# Breeze2_ESC_V1.net
KiCad netlist of a schematic drawn in Altium Designer
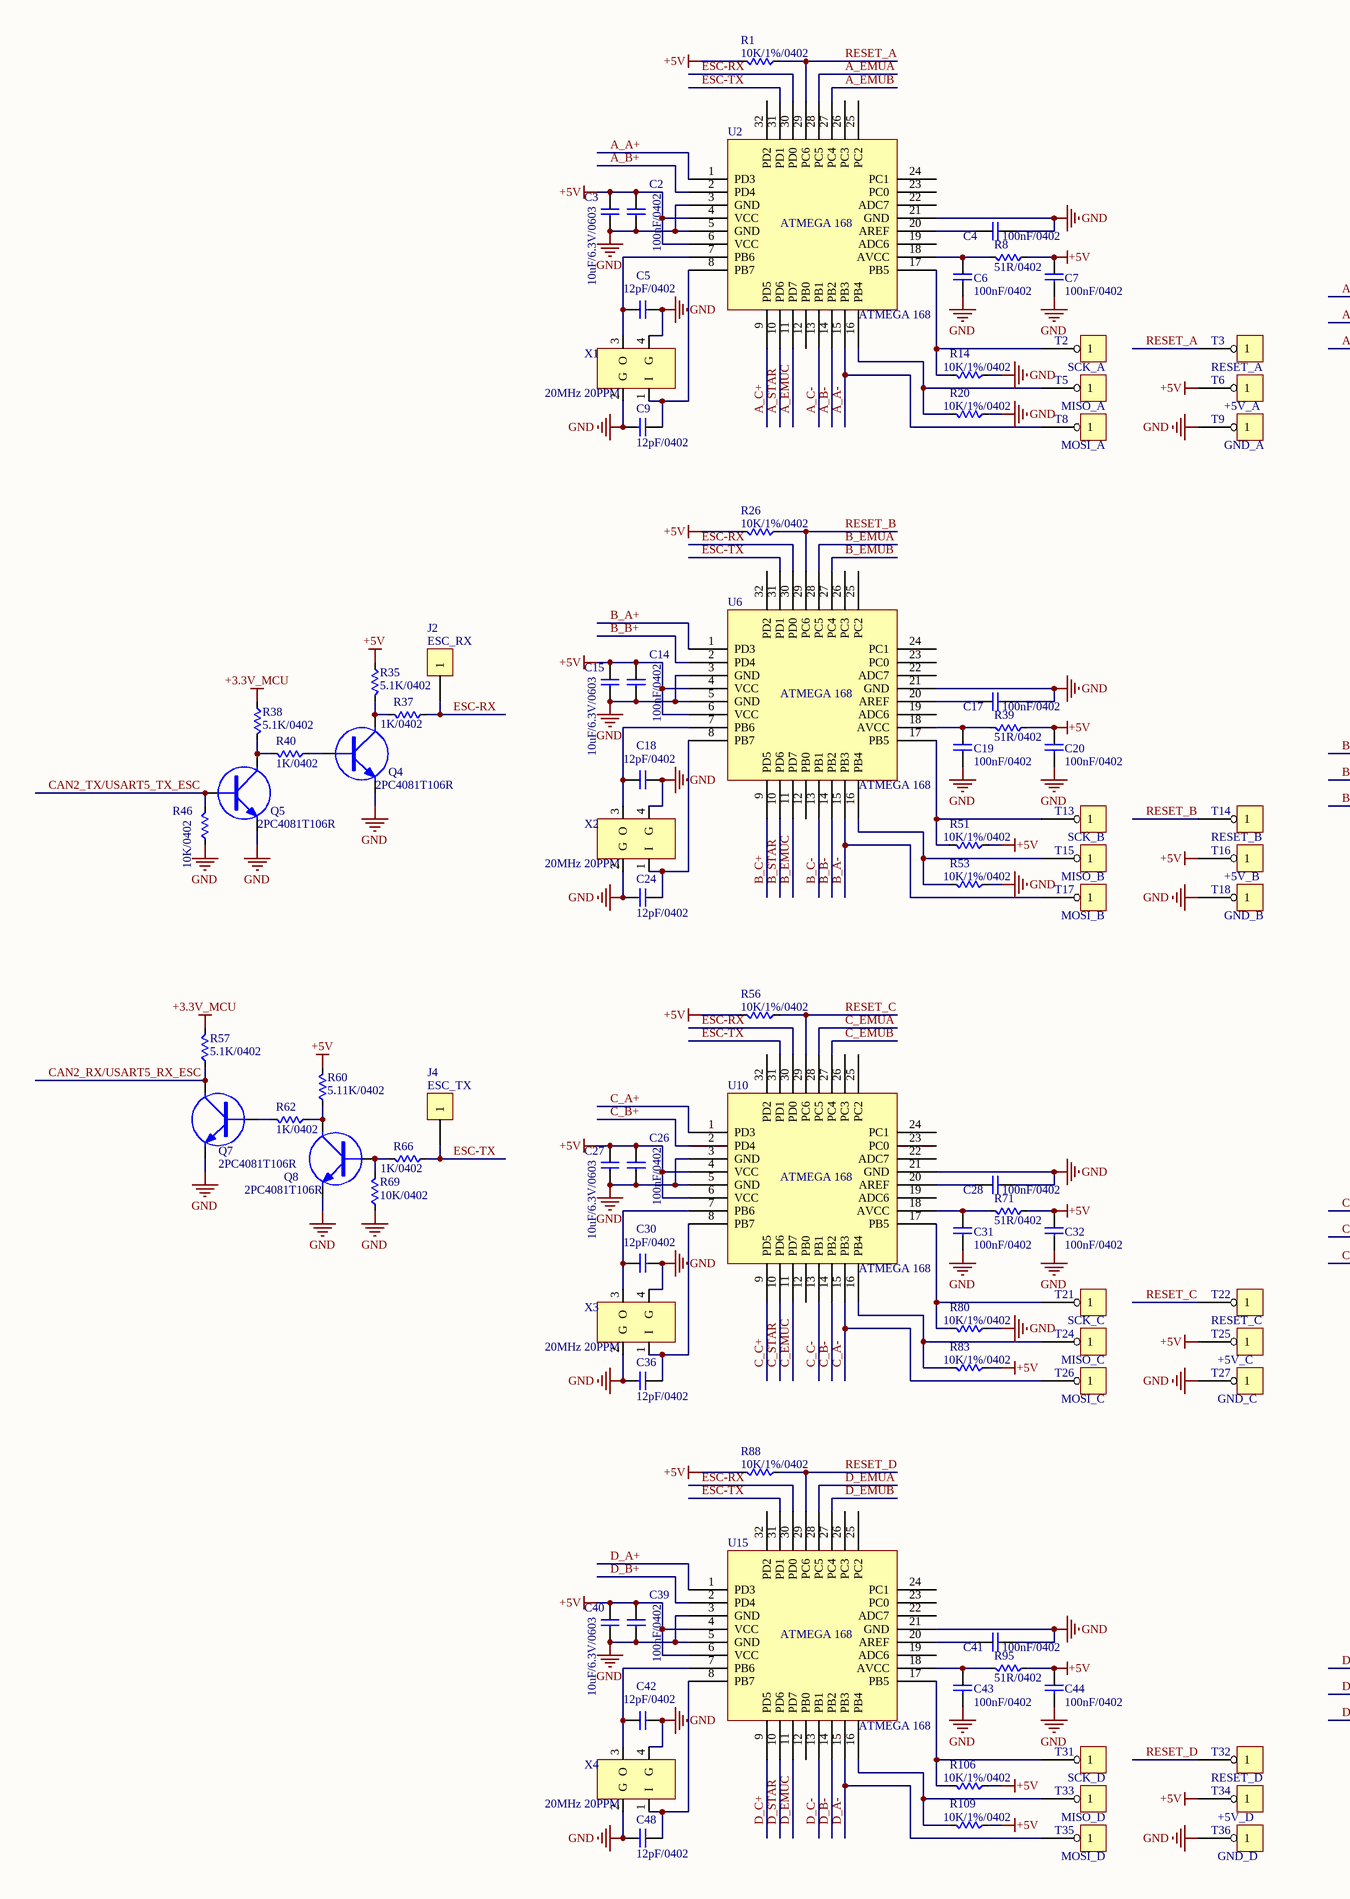
[diagram p0: Breeze2 ESC V1.SchDoc, left]
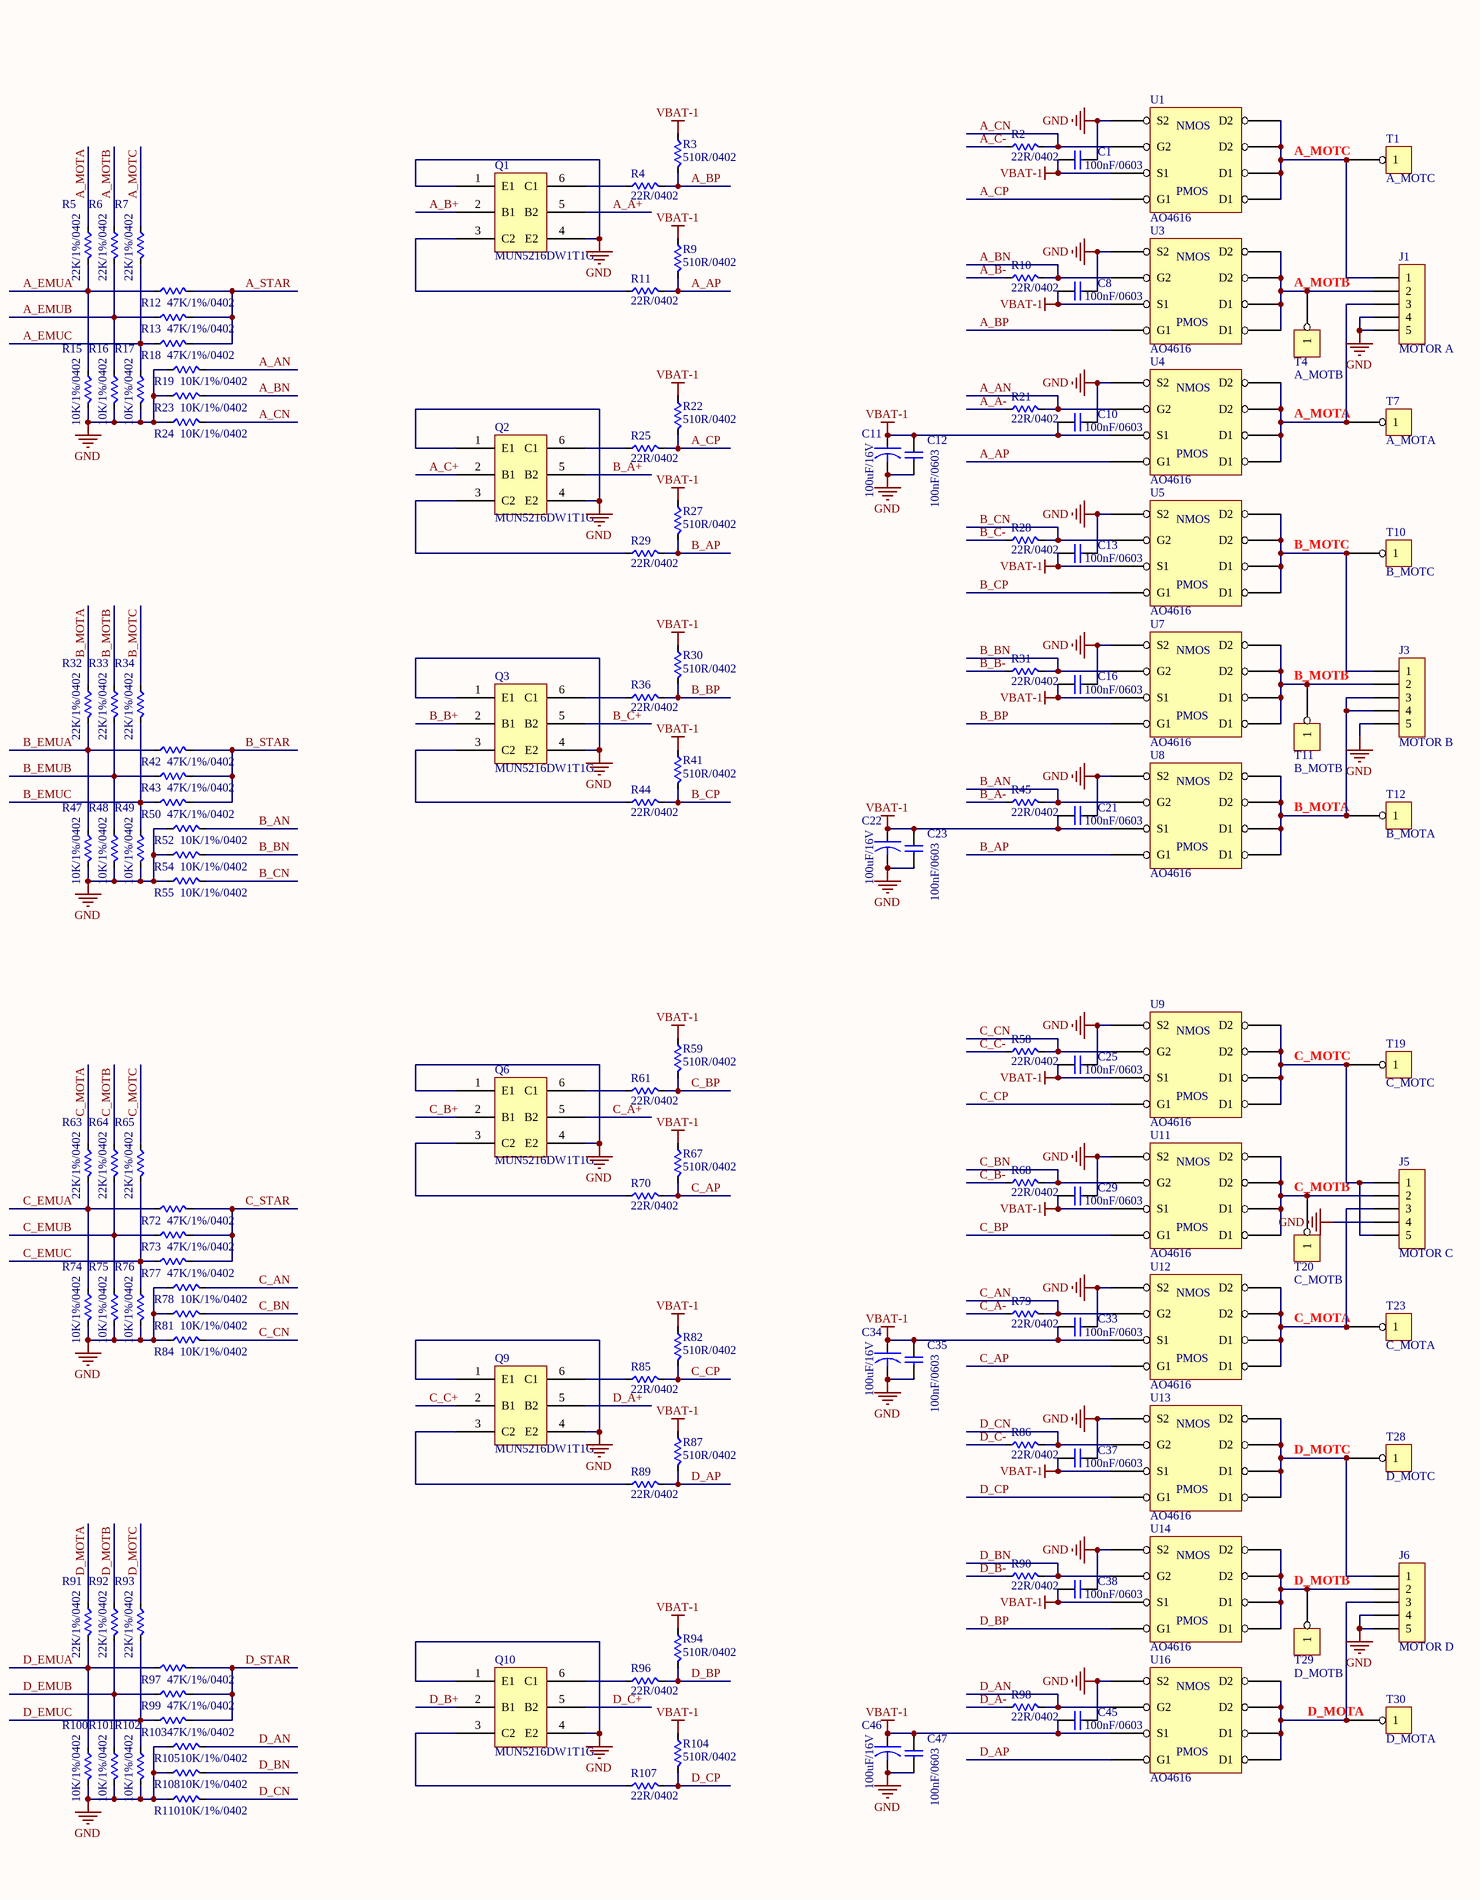
[diagram p1: Breeze2 ESC V1.SchDoc, right]

(export (version "E")
  (design (tool "Eeschema 10.0.6"))
  (components
    (comp (ref "C1")
      (value "100nF/0603")
      (footprint "0603C-S")
      (description "CAP")
      (libsource (lib "YUNEEC-SCH") (part "CAP"))
    )
    (comp (ref "C2")
      (value "100nF/0402")
      (footprint "0402C-S")
      (description "CAP")
      (libsource (lib "YUNEEC-SCH") (part "CAP"))
    )
    (comp (ref "C3")
      (value "10uF/6.3V/0603")
      (footprint "0603C-S")
      (description "CAP")
      (libsource (lib "YUNEEC-SCH") (part "CAP"))
    )
    (comp (ref "C4")
      (value "100nF/0402")
      (footprint "0402C-S")
      (description "CAP")
      (libsource (lib "YUNEEC-SCH") (part "CAP"))
    )
    (comp (ref "C5")
      (value "12pF/0402")
      (footprint "0402C-S")
      (description "CAP")
      (libsource (lib "YUNEEC-SCH") (part "CAP"))
    )
    (comp (ref "C6")
      (value "100nF/0402")
      (footprint "0402C-S")
      (description "CAP")
      (libsource (lib "YUNEEC-SCH") (part "CAP"))
    )
    (comp (ref "C7")
      (value "100nF/0402")
      (footprint "0402C-S")
      (description "CAP")
      (libsource (lib "YUNEEC-SCH") (part "CAP"))
    )
    (comp (ref "C8")
      (value "100nF/0603")
      (footprint "0603C-S")
      (description "CAP")
      (libsource (lib "YUNEEC-SCH") (part "CAP"))
    )
    (comp (ref "C9")
      (value "12pF/0402")
      (footprint "0402C-S")
      (description "CAP")
      (libsource (lib "YUNEEC-SCH") (part "CAP"))
    )
    (comp (ref "C10")
      (value "100nF/0603")
      (footprint "0603C-S")
      (description "CAP")
      (libsource (lib "YUNEEC-SCH") (part "CAP"))
    )
    (comp (ref "C11")
      (value "100uF/16V")
      (footprint "1210C-S")
      (description "Capacitor")
      (libsource (lib "*") (part "CAPACITOR"))
    )
    (comp (ref "C12")
      (value "100nF/0603")
      (footprint "0603C-S")
      (description "CAP")
      (libsource (lib "YUNEEC-SCH") (part "CAP"))
    )
    (comp (ref "C13")
      (value "100nF/0603")
      (footprint "0603C-S")
      (description "CAP")
      (libsource (lib "YUNEEC-SCH") (part "CAP"))
    )
    (comp (ref "C14")
      (value "100nF/0402")
      (footprint "0402C-S")
      (description "CAP")
      (libsource (lib "YUNEEC-SCH") (part "CAP"))
    )
    (comp (ref "C15")
      (value "10uF/6.3V/0603")
      (footprint "0603C-S")
      (description "CAP")
      (libsource (lib "YUNEEC-SCH") (part "CAP"))
    )
    (comp (ref "C16")
      (value "100nF/0603")
      (footprint "0603C-S")
      (description "CAP")
      (libsource (lib "YUNEEC-SCH") (part "CAP"))
    )
    (comp (ref "C17")
      (value "100nF/0402")
      (footprint "0402C-S")
      (description "CAP")
      (libsource (lib "YUNEEC-SCH") (part "CAP"))
    )
    (comp (ref "C18")
      (value "12pF/0402")
      (footprint "0402C-S")
      (description "CAP")
      (libsource (lib "YUNEEC-SCH") (part "CAP"))
    )
    (comp (ref "C19")
      (value "100nF/0402")
      (footprint "0402C-S")
      (description "CAP")
      (libsource (lib "YUNEEC-SCH") (part "CAP"))
    )
    (comp (ref "C20")
      (value "100nF/0402")
      (footprint "0402C-S")
      (description "CAP")
      (libsource (lib "YUNEEC-SCH") (part "CAP"))
    )
    (comp (ref "C21")
      (value "100nF/0603")
      (footprint "0603C-S")
      (description "CAP")
      (libsource (lib "YUNEEC-SCH") (part "CAP"))
    )
    (comp (ref "C22")
      (value "100uF/16V")
      (footprint "1210C-S")
      (description "Capacitor")
      (libsource (lib "*") (part "CAPACITOR"))
    )
    (comp (ref "C23")
      (value "100nF/0603")
      (footprint "0603C-S")
      (description "CAP")
      (libsource (lib "YUNEEC-SCH") (part "CAP"))
    )
    (comp (ref "C24")
      (value "12pF/0402")
      (footprint "0402C-S")
      (description "CAP")
      (libsource (lib "YUNEEC-SCH") (part "CAP"))
    )
    (comp (ref "C25")
      (value "100nF/0603")
      (footprint "0603C-S")
      (description "CAP")
      (libsource (lib "YUNEEC-SCH") (part "CAP"))
    )
    (comp (ref "C26")
      (value "100nF/0402")
      (footprint "0402C-S")
      (description "CAP")
      (libsource (lib "YUNEEC-SCH") (part "CAP"))
    )
    (comp (ref "C27")
      (value "10uF/6.3V/0603")
      (footprint "0603C-S")
      (description "CAP")
      (libsource (lib "YUNEEC-SCH") (part "CAP"))
    )
    (comp (ref "C28")
      (value "100nF/0402")
      (footprint "0402C-S")
      (description "CAP")
      (libsource (lib "YUNEEC-SCH") (part "CAP"))
    )
    (comp (ref "C29")
      (value "100nF/0603")
      (footprint "0603C-S")
      (description "CAP")
      (libsource (lib "YUNEEC-SCH") (part "CAP"))
    )
    (comp (ref "C30")
      (value "12pF/0402")
      (footprint "0402C-S")
      (description "CAP")
      (libsource (lib "YUNEEC-SCH") (part "CAP"))
    )
    (comp (ref "C31")
      (value "100nF/0402")
      (footprint "0402C-S")
      (description "CAP")
      (libsource (lib "YUNEEC-SCH") (part "CAP"))
    )
    (comp (ref "C32")
      (value "100nF/0402")
      (footprint "0402C-S")
      (description "CAP")
      (libsource (lib "YUNEEC-SCH") (part "CAP"))
    )
    (comp (ref "C33")
      (value "100nF/0603")
      (footprint "0603C-S")
      (description "CAP")
      (libsource (lib "YUNEEC-SCH") (part "CAP"))
    )
    (comp (ref "C34")
      (value "100uF/16V")
      (footprint "1210C-S")
      (description "Capacitor")
      (libsource (lib "*") (part "CAPACITOR"))
    )
    (comp (ref "C35")
      (value "100nF/0603")
      (footprint "0603C-S")
      (description "CAP")
      (libsource (lib "YUNEEC-SCH") (part "CAP"))
    )
    (comp (ref "C36")
      (value "12pF/0402")
      (footprint "0402C-S")
      (description "CAP")
      (libsource (lib "YUNEEC-SCH") (part "CAP"))
    )
    (comp (ref "C37")
      (value "100nF/0603")
      (footprint "0603C-S")
      (description "CAP")
      (libsource (lib "YUNEEC-SCH") (part "CAP"))
    )
    (comp (ref "C38")
      (value "100nF/0603")
      (footprint "0603C-S")
      (description "CAP")
      (libsource (lib "YUNEEC-SCH") (part "CAP"))
    )
    (comp (ref "C39")
      (value "100nF/0402")
      (footprint "0402C-S")
      (description "CAP")
      (libsource (lib "YUNEEC-SCH") (part "CAP"))
    )
    (comp (ref "C40")
      (value "10uF/6.3V/0603")
      (footprint "0603C-S")
      (description "CAP")
      (libsource (lib "YUNEEC-SCH") (part "CAP"))
    )
    (comp (ref "C41")
      (value "100nF/0402")
      (footprint "0402C-S")
      (description "CAP")
      (libsource (lib "YUNEEC-SCH") (part "CAP"))
    )
    (comp (ref "C42")
      (value "12pF/0402")
      (footprint "0402C-S")
      (description "CAP")
      (libsource (lib "YUNEEC-SCH") (part "CAP"))
    )
    (comp (ref "C43")
      (value "100nF/0402")
      (footprint "0402C-S")
      (description "CAP")
      (libsource (lib "YUNEEC-SCH") (part "CAP"))
    )
    (comp (ref "C44")
      (value "100nF/0402")
      (footprint "0402C-S")
      (description "CAP")
      (libsource (lib "YUNEEC-SCH") (part "CAP"))
    )
    (comp (ref "C45")
      (value "100nF/0603")
      (footprint "0603C-S")
      (description "CAP")
      (libsource (lib "YUNEEC-SCH") (part "CAP"))
    )
    (comp (ref "C46")
      (value "100uF/16V")
      (footprint "1210C-S")
      (description "Capacitor")
      (libsource (lib "*") (part "CAPACITOR"))
    )
    (comp (ref "C47")
      (value "100nF/0603")
      (footprint "0603C-S")
      (description "CAP")
      (libsource (lib "YUNEEC-SCH") (part "CAP"))
    )
    (comp (ref "C48")
      (value "12pF/0402")
      (footprint "0402C-S")
      (description "CAP")
      (libsource (lib "YUNEEC-SCH") (part "CAP"))
    )
    (comp (ref "J1")
      (value "MOTOR A")
      (footprint "1.5*3PIN/SMD-H")
      (description "Connector")
      (libsource (lib "YUNEEC-SCH") (part "CON5"))
    )
    (comp (ref "J2")
      (value "ESC_RX")
      (footprint "TPJ1.2")
      (description "Connector")
      (libsource (lib "*") (part "CON1"))
    )
    (comp (ref "J3")
      (value "MOTOR B")
      (footprint "1.5*3PIN/SMD-H")
      (description "Connector")
      (libsource (lib "YUNEEC-SCH") (part "CON5"))
    )
    (comp (ref "J4")
      (value "ESC_TX")
      (footprint "TPJ1.2")
      (description "Connector")
      (libsource (lib "*") (part "CON1"))
    )
    (comp (ref "J5")
      (value "MOTOR C")
      (footprint "1.5*3PIN/SMD-H")
      (description "Connector")
      (libsource (lib "YUNEEC-SCH") (part "CON5"))
    )
    (comp (ref "J6")
      (value "MOTOR D")
      (footprint "1.5*3PIN/SMD-H")
      (description "Connector")
      (libsource (lib "YUNEEC-SCH") (part "CON5"))
    )
    (comp (ref "Q1") (value "MUN5216DW1T1G") (footprint "SOT-363A") (libsource (lib "*") (part "NPN_6")))
    (comp (ref "Q2") (value "MUN5216DW1T1G") (footprint "SOT-363A") (libsource (lib "*") (part "NPN_6")))
    (comp (ref "Q3") (value "MUN5216DW1T1G") (footprint "SOT-363A") (libsource (lib "*") (part "NPN_6")))
    (comp (ref "Q4")
      (value "2PC4081T106R")
      (footprint "SOT-323A")
      (description "NPN Transistor")
      (libsource (lib "YUNEEC-SCH") (part "NPN"))
    )
    (comp (ref "Q5")
      (value "2PC4081T106R")
      (footprint "SOT-323A")
      (description "NPN Transistor")
      (libsource (lib "YUNEEC-SCH") (part "NPN"))
    )
    (comp (ref "Q6") (value "MUN5216DW1T1G") (footprint "SOT-363A") (libsource (lib "*") (part "NPN_6")))
    (comp (ref "Q7")
      (value "2PC4081T106R")
      (footprint "SOT-323A")
      (description "NPN Transistor")
      (libsource (lib "YUNEEC-SCH") (part "NPN"))
    )
    (comp (ref "Q8")
      (value "2PC4081T106R")
      (footprint "SOT-323A")
      (description "NPN Transistor")
      (libsource (lib "YUNEEC-SCH") (part "NPN"))
    )
    (comp (ref "Q9") (value "MUN5216DW1T1G") (footprint "SOT-363A") (libsource (lib "*") (part "NPN_6")))
    (comp (ref "Q10") (value "MUN5216DW1T1G") (footprint "SOT-363A") (libsource (lib "*") (part "NPN_6")))
    (comp (ref "R1") (value "10K/1%/0402") (footprint "0402R-S") (libsource (lib "YUNEEC-SCH") (part "RES")))
    (comp (ref "R2") (value "22R/0402") (footprint "0402R-S") (libsource (lib "YUNEEC-SCH") (part "RES")))
    (comp (ref "R3") (value "510R/0402") (footprint "0402R-S") (libsource (lib "YUNEEC-SCH") (part "RES")))
    (comp (ref "R4") (value "22R/0402") (footprint "0402R-S") (libsource (lib "YUNEEC-SCH") (part "RES")))
    (comp (ref "R5") (value "22K/1%/0402") (footprint "0402R-S") (libsource (lib "YUNEEC-SCH") (part "RES")))
    (comp (ref "R6") (value "22K/1%/0402") (footprint "0402R-S") (libsource (lib "YUNEEC-SCH") (part "RES")))
    (comp (ref "R7") (value "22K/1%/0402") (footprint "0402R-S") (libsource (lib "YUNEEC-SCH") (part "RES")))
    (comp (ref "R8") (value "51R/0402") (footprint "0402R-S") (libsource (lib "YUNEEC-SCH") (part "RES")))
    (comp (ref "R9") (value "510R/0402") (footprint "0402R-S") (libsource (lib "YUNEEC-SCH") (part "RES")))
    (comp (ref "R10") (value "22R/0402") (footprint "0402R-S") (libsource (lib "YUNEEC-SCH") (part "RES")))
    (comp (ref "R11") (value "22R/0402") (footprint "0402R-S") (libsource (lib "YUNEEC-SCH") (part "RES")))
    (comp (ref "R12") (value "47K/1%/0402") (footprint "0402R-S") (libsource (lib "YUNEEC-SCH") (part "RES")))
    (comp (ref "R13") (value "47K/1%/0402") (footprint "0402R-S") (libsource (lib "YUNEEC-SCH") (part "RES")))
    (comp (ref "R14") (value "10K/1%/0402") (footprint "0402R-S") (libsource (lib "YUNEEC-SCH") (part "RES")))
    (comp (ref "R15") (value "10K/1%/0402") (footprint "0402R-S") (libsource (lib "YUNEEC-SCH") (part "RES")))
    (comp (ref "R16") (value "10K/1%/0402") (footprint "0402R-S") (libsource (lib "YUNEEC-SCH") (part "RES")))
    (comp (ref "R17") (value "10K/1%/0402") (footprint "0402R-S") (libsource (lib "YUNEEC-SCH") (part "RES")))
    (comp (ref "R18") (value "47K/1%/0402") (footprint "0402R-S") (libsource (lib "YUNEEC-SCH") (part "RES")))
    (comp (ref "R19") (value "10K/1%/0402") (footprint "0402R-S") (libsource (lib "YUNEEC-SCH") (part "RES")))
    (comp (ref "R20") (value "10K/1%/0402") (footprint "0402R-S") (libsource (lib "YUNEEC-SCH") (part "RES")))
    (comp (ref "R21") (value "22R/0402") (footprint "0402R-S") (libsource (lib "YUNEEC-SCH") (part "RES")))
    (comp (ref "R22") (value "510R/0402") (footprint "0402R-S") (libsource (lib "YUNEEC-SCH") (part "RES")))
    (comp (ref "R23") (value "10K/1%/0402") (footprint "0402R-S") (libsource (lib "YUNEEC-SCH") (part "RES")))
    (comp (ref "R24") (value "10K/1%/0402") (footprint "0402R-S") (libsource (lib "YUNEEC-SCH") (part "RES")))
    (comp (ref "R25") (value "22R/0402") (footprint "0402R-S") (libsource (lib "YUNEEC-SCH") (part "RES")))
    (comp (ref "R26") (value "10K/1%/0402") (footprint "0402R-S") (libsource (lib "YUNEEC-SCH") (part "RES")))
    (comp (ref "R27") (value "510R/0402") (footprint "0402R-S") (libsource (lib "YUNEEC-SCH") (part "RES")))
    (comp (ref "R28") (value "22R/0402") (footprint "0402R-S") (libsource (lib "YUNEEC-SCH") (part "RES")))
    (comp (ref "R29") (value "22R/0402") (footprint "0402R-S") (libsource (lib "YUNEEC-SCH") (part "RES")))
    (comp (ref "R30") (value "510R/0402") (footprint "0402R-S") (libsource (lib "YUNEEC-SCH") (part "RES")))
    (comp (ref "R31") (value "22R/0402") (footprint "0402R-S") (libsource (lib "YUNEEC-SCH") (part "RES")))
    (comp (ref "R32") (value "22K/1%/0402") (footprint "0402R-S") (libsource (lib "YUNEEC-SCH") (part "RES")))
    (comp (ref "R33") (value "22K/1%/0402") (footprint "0402R-S") (libsource (lib "YUNEEC-SCH") (part "RES")))
    (comp (ref "R34") (value "22K/1%/0402") (footprint "0402R-S") (libsource (lib "YUNEEC-SCH") (part "RES")))
    (comp (ref "R35") (value "5.1K/0402") (footprint "0402R-S") (libsource (lib "YUNEEC-SCH") (part "RES")))
    (comp (ref "R36") (value "22R/0402") (footprint "0402R-S") (libsource (lib "YUNEEC-SCH") (part "RES")))
    (comp (ref "R37") (value "1K/0402") (footprint "0402R-S") (libsource (lib "YUNEEC-SCH") (part "RES")))
    (comp (ref "R38") (value "5.1K/0402") (footprint "0402R-S") (libsource (lib "YUNEEC-SCH") (part "RES")))
    (comp (ref "R39") (value "51R/0402") (footprint "0402R-S") (libsource (lib "YUNEEC-SCH") (part "RES")))
    (comp (ref "R40") (value "1K/0402") (footprint "0402R-S") (libsource (lib "YUNEEC-SCH") (part "RES")))
    (comp (ref "R41") (value "510R/0402") (footprint "0402R-S") (libsource (lib "YUNEEC-SCH") (part "RES")))
    (comp (ref "R42") (value "47K/1%/0402") (footprint "0402R-S") (libsource (lib "YUNEEC-SCH") (part "RES")))
    (comp (ref "R43") (value "47K/1%/0402") (footprint "0402R-S") (libsource (lib "YUNEEC-SCH") (part "RES")))
    (comp (ref "R44") (value "22R/0402") (footprint "0402R-S") (libsource (lib "YUNEEC-SCH") (part "RES")))
    (comp (ref "R45") (value "22R/0402") (footprint "0402R-S") (libsource (lib "YUNEEC-SCH") (part "RES")))
    (comp (ref "R46") (value "10K/0402") (footprint "0402R-S") (libsource (lib "YUNEEC-SCH") (part "RES")))
    (comp (ref "R47") (value "10K/1%/0402") (footprint "0402R-S") (libsource (lib "YUNEEC-SCH") (part "RES")))
    (comp (ref "R48") (value "10K/1%/0402") (footprint "0402R-S") (libsource (lib "YUNEEC-SCH") (part "RES")))
    (comp (ref "R49") (value "10K/1%/0402") (footprint "0402R-S") (libsource (lib "YUNEEC-SCH") (part "RES")))
    (comp (ref "R50") (value "47K/1%/0402") (footprint "0402R-S") (libsource (lib "YUNEEC-SCH") (part "RES")))
    (comp (ref "R51") (value "10K/1%/0402") (footprint "0402R-S") (libsource (lib "YUNEEC-SCH") (part "RES")))
    (comp (ref "R52") (value "10K/1%/0402") (footprint "0402R-S") (libsource (lib "YUNEEC-SCH") (part "RES")))
    (comp (ref "R53") (value "10K/1%/0402") (footprint "0402R-S") (libsource (lib "YUNEEC-SCH") (part "RES")))
    (comp (ref "R54") (value "10K/1%/0402") (footprint "0402R-S") (libsource (lib "YUNEEC-SCH") (part "RES")))
    (comp (ref "R55") (value "10K/1%/0402") (footprint "0402R-S") (libsource (lib "YUNEEC-SCH") (part "RES")))
    (comp (ref "R56") (value "10K/1%/0402") (footprint "0402R-S") (libsource (lib "YUNEEC-SCH") (part "RES")))
    (comp (ref "R57") (value "5.1K/0402") (footprint "0402R-S") (libsource (lib "YUNEEC-SCH") (part "RES")))
    (comp (ref "R58") (value "22R/0402") (footprint "0402R-S") (libsource (lib "YUNEEC-SCH") (part "RES")))
    (comp (ref "R59") (value "510R/0402") (footprint "0402R-S") (libsource (lib "YUNEEC-SCH") (part "RES")))
    (comp (ref "R60") (value "5.11K/0402") (footprint "0402R-S") (libsource (lib "YUNEEC-SCH") (part "RES")))
    (comp (ref "R61") (value "22R/0402") (footprint "0402R-S") (libsource (lib "YUNEEC-SCH") (part "RES")))
    (comp (ref "R62") (value "1K/0402") (footprint "0402R-S") (libsource (lib "YUNEEC-SCH") (part "RES")))
    (comp (ref "R63") (value "22K/1%/0402") (footprint "0402R-S") (libsource (lib "YUNEEC-SCH") (part "RES")))
    (comp (ref "R64") (value "22K/1%/0402") (footprint "0402R-S") (libsource (lib "YUNEEC-SCH") (part "RES")))
    (comp (ref "R65") (value "22K/1%/0402") (footprint "0402R-S") (libsource (lib "YUNEEC-SCH") (part "RES")))
    (comp (ref "R66") (value "1K/0402") (footprint "0402R-S") (libsource (lib "YUNEEC-SCH") (part "RES")))
    (comp (ref "R67") (value "510R/0402") (footprint "0402R-S") (libsource (lib "YUNEEC-SCH") (part "RES")))
    (comp (ref "R68") (value "22R/0402") (footprint "0402R-S") (libsource (lib "YUNEEC-SCH") (part "RES")))
    (comp (ref "R69") (value "10K/0402") (footprint "0402R-S") (libsource (lib "YUNEEC-SCH") (part "RES")))
    (comp (ref "R70") (value "22R/0402") (footprint "0402R-S") (libsource (lib "YUNEEC-SCH") (part "RES")))
    (comp (ref "R71") (value "51R/0402") (footprint "0402R-S") (libsource (lib "YUNEEC-SCH") (part "RES")))
    (comp (ref "R72") (value "47K/1%/0402") (footprint "0402R-S") (libsource (lib "YUNEEC-SCH") (part "RES")))
    (comp (ref "R73") (value "47K/1%/0402") (footprint "0402R-S") (libsource (lib "YUNEEC-SCH") (part "RES")))
    (comp (ref "R74") (value "10K/1%/0402") (footprint "0402R-S") (libsource (lib "YUNEEC-SCH") (part "RES")))
    (comp (ref "R75") (value "10K/1%/0402") (footprint "0402R-S") (libsource (lib "YUNEEC-SCH") (part "RES")))
    (comp (ref "R76") (value "10K/1%/0402") (footprint "0402R-S") (libsource (lib "YUNEEC-SCH") (part "RES")))
    (comp (ref "R77") (value "47K/1%/0402") (footprint "0402R-S") (libsource (lib "YUNEEC-SCH") (part "RES")))
    (comp (ref "R78") (value "10K/1%/0402") (footprint "0402R-S") (libsource (lib "YUNEEC-SCH") (part "RES")))
    (comp (ref "R79") (value "22R/0402") (footprint "0402R-S") (libsource (lib "YUNEEC-SCH") (part "RES")))
    (comp (ref "R80") (value "10K/1%/0402") (footprint "0402R-S") (libsource (lib "YUNEEC-SCH") (part "RES")))
    (comp (ref "R81") (value "10K/1%/0402") (footprint "0402R-S") (libsource (lib "YUNEEC-SCH") (part "RES")))
    (comp (ref "R82") (value "510R/0402") (footprint "0402R-S") (libsource (lib "YUNEEC-SCH") (part "RES")))
    (comp (ref "R83") (value "10K/1%/0402") (footprint "0402R-S") (libsource (lib "YUNEEC-SCH") (part "RES")))
    (comp (ref "R84") (value "10K/1%/0402") (footprint "0402R-S") (libsource (lib "YUNEEC-SCH") (part "RES")))
    (comp (ref "R85") (value "22R/0402") (footprint "0402R-S") (libsource (lib "YUNEEC-SCH") (part "RES")))
    (comp (ref "R86") (value "22R/0402") (footprint "0402R-S") (libsource (lib "YUNEEC-SCH") (part "RES")))
    (comp (ref "R87") (value "510R/0402") (footprint "0402R-S") (libsource (lib "YUNEEC-SCH") (part "RES")))
    (comp (ref "R88") (value "10K/1%/0402") (footprint "0402R-S") (libsource (lib "YUNEEC-SCH") (part "RES")))
    (comp (ref "R89") (value "22R/0402") (footprint "0402R-S") (libsource (lib "YUNEEC-SCH") (part "RES")))
    (comp (ref "R90") (value "22R/0402") (footprint "0402R-S") (libsource (lib "YUNEEC-SCH") (part "RES")))
    (comp (ref "R91") (value "22K/1%/0402") (footprint "0402R-S") (libsource (lib "YUNEEC-SCH") (part "RES")))
    (comp (ref "R92") (value "22K/1%/0402") (footprint "0402R-S") (libsource (lib "YUNEEC-SCH") (part "RES")))
    (comp (ref "R93") (value "22K/1%/0402") (footprint "0402R-S") (libsource (lib "YUNEEC-SCH") (part "RES")))
    (comp (ref "R94") (value "510R/0402") (footprint "0402R-S") (libsource (lib "YUNEEC-SCH") (part "RES")))
    (comp (ref "R95") (value "51R/0402") (footprint "0402R-S") (libsource (lib "YUNEEC-SCH") (part "RES")))
    (comp (ref "R96") (value "22R/0402") (footprint "0402R-S") (libsource (lib "YUNEEC-SCH") (part "RES")))
    (comp (ref "R97") (value "47K/1%/0402") (footprint "0402R-S") (libsource (lib "YUNEEC-SCH") (part "RES")))
    (comp (ref "R98") (value "22R/0402") (footprint "0402R-S") (libsource (lib "YUNEEC-SCH") (part "RES")))
    (comp (ref "R99") (value "47K/1%/0402") (footprint "0402R-S") (libsource (lib "YUNEEC-SCH") (part "RES")))
    (comp (ref "R100")
      (value "10K/1%/0402")
      (footprint "0402R-S")
      (libsource (lib "YUNEEC-SCH") (part "RES"))
    )
    (comp (ref "R101")
      (value "10K/1%/0402")
      (footprint "0402R-S")
      (libsource (lib "YUNEEC-SCH") (part "RES"))
    )
    (comp (ref "R102")
      (value "10K/1%/0402")
      (footprint "0402R-S")
      (libsource (lib "YUNEEC-SCH") (part "RES"))
    )
    (comp (ref "R103")
      (value "47K/1%/0402")
      (footprint "0402R-S")
      (libsource (lib "YUNEEC-SCH") (part "RES"))
    )
    (comp (ref "R104") (value "510R/0402") (footprint "0402R-S") (libsource (lib "YUNEEC-SCH") (part "RES")))
    (comp (ref "R105")
      (value "10K/1%/0402")
      (footprint "0402R-S")
      (libsource (lib "YUNEEC-SCH") (part "RES"))
    )
    (comp (ref "R106")
      (value "10K/1%/0402")
      (footprint "0402R-S")
      (libsource (lib "YUNEEC-SCH") (part "RES"))
    )
    (comp (ref "R107") (value "22R/0402") (footprint "0402R-S") (libsource (lib "YUNEEC-SCH") (part "RES")))
    (comp (ref "R108")
      (value "10K/1%/0402")
      (footprint "0402R-S")
      (libsource (lib "YUNEEC-SCH") (part "RES"))
    )
    (comp (ref "R109")
      (value "10K/1%/0402")
      (footprint "0402R-S")
      (libsource (lib "YUNEEC-SCH") (part "RES"))
    )
    (comp (ref "R110")
      (value "10K/1%/0402")
      (footprint "0402R-S")
      (libsource (lib "YUNEEC-SCH") (part "RES"))
    )
    (comp (ref "T1") (value "A_MOTC") (footprint "TPJ1.5") (libsource (lib "*") (part "HEADER1")))
    (comp (ref "T2") (value "SCK_A") (footprint "TPJ1.2") (libsource (lib "*") (part "HEADER1")))
    (comp (ref "T3") (value "RESET_A") (footprint "TPJ1.2") (libsource (lib "*") (part "HEADER1")))
    (comp (ref "T4") (value "A_MOTB") (footprint "TPJ1.5") (libsource (lib "") (part "HEADER1_1")))
    (comp (ref "T5") (value "MISO_A") (footprint "TPJ1.2") (libsource (lib "*") (part "HEADER1")))
    (comp (ref "T6") (value "+5V_A") (footprint "TPJ1.2") (libsource (lib "*") (part "HEADER1")))
    (comp (ref "T7") (value "A_MOTA") (footprint "TPJ1.5") (libsource (lib "*") (part "HEADER1")))
    (comp (ref "T8") (value "MOSI_A") (footprint "TPJ1.2") (libsource (lib "*") (part "HEADER1")))
    (comp (ref "T9") (value "GND_A") (footprint "TPJ1.2") (libsource (lib "*") (part "HEADER1")))
    (comp (ref "T10") (value "B_MOTC") (footprint "TPJ1.5") (libsource (lib "*") (part "HEADER1")))
    (comp (ref "T11") (value "B_MOTB") (footprint "TPJ1.5") (libsource (lib "") (part "HEADER1_1")))
    (comp (ref "T12") (value "B_MOTA") (footprint "TPJ1.5") (libsource (lib "*") (part "HEADER1")))
    (comp (ref "T13") (value "SCK_B") (footprint "TPJ1.2") (libsource (lib "*") (part "HEADER1")))
    (comp (ref "T14") (value "RESET_B") (footprint "TPJ1.2") (libsource (lib "*") (part "HEADER1")))
    (comp (ref "T15") (value "MISO_B") (footprint "TPJ1.2") (libsource (lib "*") (part "HEADER1")))
    (comp (ref "T16") (value "+5V_B") (footprint "TPJ1.2") (libsource (lib "*") (part "HEADER1")))
    (comp (ref "T17") (value "MOSI_B") (footprint "TPJ1.2") (libsource (lib "*") (part "HEADER1")))
    (comp (ref "T18") (value "GND_B") (footprint "TPJ1.2") (libsource (lib "*") (part "HEADER1")))
    (comp (ref "T19") (value "C_MOTC") (footprint "TPJ1.5") (libsource (lib "*") (part "HEADER1")))
    (comp (ref "T20") (value "C_MOTB") (footprint "TPJ1.5") (libsource (lib "") (part "HEADER1_1")))
    (comp (ref "T21") (value "SCK_C") (footprint "TPJ1.2") (libsource (lib "*") (part "HEADER1")))
    (comp (ref "T22") (value "RESET_C") (footprint "TPJ1.2") (libsource (lib "*") (part "HEADER1")))
    (comp (ref "T23") (value "C_MOTA") (footprint "TPJ1.5") (libsource (lib "*") (part "HEADER1")))
    (comp (ref "T24") (value "MISO_C") (footprint "TPJ1.2") (libsource (lib "*") (part "HEADER1")))
    (comp (ref "T25") (value "+5V_C") (footprint "TPJ1.2") (libsource (lib "*") (part "HEADER1")))
    (comp (ref "T26") (value "MOSI_C") (footprint "TPJ1.2") (libsource (lib "*") (part "HEADER1")))
    (comp (ref "T27") (value "GND_C") (footprint "TPJ1.2") (libsource (lib "*") (part "HEADER1")))
    (comp (ref "T28") (value "D_MOTC") (footprint "TPJ1.5") (libsource (lib "*") (part "HEADER1")))
    (comp (ref "T29") (value "D_MOTB") (footprint "TPJ1.5") (libsource (lib "") (part "HEADER1_1")))
    (comp (ref "T30") (value "D_MOTA") (footprint "TPJ1.5") (libsource (lib "*") (part "HEADER1")))
    (comp (ref "T31") (value "SCK_D") (footprint "TPJ1.2") (libsource (lib "*") (part "HEADER1")))
    (comp (ref "T32") (value "RESET_D") (footprint "TPJ1.2") (libsource (lib "*") (part "HEADER1")))
    (comp (ref "T33") (value "MISO_D") (footprint "TPJ1.2") (libsource (lib "*") (part "HEADER1")))
    (comp (ref "T34") (value "+5V_D") (footprint "TPJ1.2") (libsource (lib "*") (part "HEADER1")))
    (comp (ref "T35") (value "MOSI_D") (footprint "TPJ1.2") (libsource (lib "*") (part "HEADER1")))
    (comp (ref "T36") (value "GND_D") (footprint "TPJ1.2") (libsource (lib "*") (part "HEADER1")))
    (comp (ref "U1") (value "AO4616") (footprint "SO-8A") (libsource (lib "*") (part "AO4616")))
    (comp (ref "U2") (value "ATMEGA 168") (footprint "QFN32/5*5") (libsource (lib "*") (part "ATMEGA 168")))
    (comp (ref "U3") (value "AO4616") (footprint "SO-8A") (libsource (lib "*") (part "AO4616")))
    (comp (ref "U4") (value "AO4616") (footprint "SO-8A") (libsource (lib "*") (part "AO4616")))
    (comp (ref "U5") (value "AO4616") (footprint "SO-8A") (libsource (lib "*") (part "AO4616")))
    (comp (ref "U6") (value "ATMEGA 168") (footprint "QFN32/5*5") (libsource (lib "*") (part "ATMEGA 168")))
    (comp (ref "U7") (value "AO4616") (footprint "SO-8A") (libsource (lib "*") (part "AO4616")))
    (comp (ref "U8") (value "AO4616") (footprint "SO-8A") (libsource (lib "*") (part "AO4616")))
    (comp (ref "U9") (value "AO4616") (footprint "SO-8A") (libsource (lib "*") (part "AO4616")))
    (comp (ref "U10") (value "ATMEGA 168") (footprint "QFN32/5*5") (libsource (lib "*") (part "ATMEGA 168")))
    (comp (ref "U11") (value "AO4616") (footprint "SO-8A") (libsource (lib "*") (part "AO4616")))
    (comp (ref "U12") (value "AO4616") (footprint "SO-8A") (libsource (lib "*") (part "AO4616")))
    (comp (ref "U13") (value "AO4616") (footprint "SO-8A") (libsource (lib "*") (part "AO4616")))
    (comp (ref "U14") (value "AO4616") (footprint "SO-8A") (libsource (lib "*") (part "AO4616")))
    (comp (ref "U15") (value "ATMEGA 168") (footprint "QFN32/5*5") (libsource (lib "*") (part "ATMEGA 168")))
    (comp (ref "U16") (value "AO4616") (footprint "SO-8A") (libsource (lib "*") (part "AO4616")))
    (comp (ref "X1") (value "20MHz 20PPM") (footprint "Y3225") (libsource (lib "*") (part "CON4A_1")))
    (comp (ref "X2") (value "20MHz 20PPM") (footprint "Y3225") (libsource (lib "*") (part "CON4A_1")))
    (comp (ref "X3") (value "20MHz 20PPM") (footprint "Y3225") (libsource (lib "*") (part "CON4A_1")))
    (comp (ref "X4") (value "20MHz 20PPM") (footprint "Y3225") (libsource (lib "*") (part "CON4A_1")))
  )
  (nets
    (net (code "1") (name "+3.3V_MCU") (class "Default")
      (node (ref "R38") (pin "2") (pinfunction "2_2") (pintype "passive"))
      (node (ref "R57") (pin "2") (pinfunction "2_2") (pintype "passive"))
    )
    (net (code "2") (name "+5V") (class "Default")
      (node (ref "C14") (pin "1") (pinfunction "1_1") (pintype "passive"))
      (node (ref "C15") (pin "1") (pinfunction "1_1") (pintype "passive"))
      (node (ref "C2") (pin "1") (pinfunction "1_1") (pintype "passive"))
      (node (ref "C20") (pin "1") (pinfunction "1_1") (pintype "passive"))
      (node (ref "C26") (pin "1") (pinfunction "1_1") (pintype "passive"))
      (node (ref "C27") (pin "1") (pinfunction "1_1") (pintype "passive"))
      (node (ref "C3") (pin "1") (pinfunction "1_1") (pintype "passive"))
      (node (ref "C32") (pin "1") (pinfunction "1_1") (pintype "passive"))
      (node (ref "C39") (pin "1") (pinfunction "1_1") (pintype "passive"))
      (node (ref "C40") (pin "1") (pinfunction "1_1") (pintype "passive"))
      (node (ref "C44") (pin "1") (pinfunction "1_1") (pintype "passive"))
      (node (ref "C7") (pin "1") (pinfunction "1_1") (pintype "passive"))
      (node (ref "R1") (pin "2") (pinfunction "2_2") (pintype "passive"))
      (node (ref "R106") (pin "1") (pinfunction "1_1") (pintype "passive"))
      (node (ref "R109") (pin "1") (pinfunction "1_1") (pintype "passive"))
      (node (ref "R26") (pin "2") (pinfunction "2_2") (pintype "passive"))
      (node (ref "R35") (pin "2") (pinfunction "2_2") (pintype "passive"))
      (node (ref "R39") (pin "1") (pinfunction "1_1") (pintype "passive"))
      (node (ref "R51") (pin "1") (pinfunction "1_1") (pintype "passive"))
      (node (ref "R56") (pin "2") (pinfunction "2_2") (pintype "passive"))
      (node (ref "R60") (pin "2") (pinfunction "2_2") (pintype "passive"))
      (node (ref "R71") (pin "1") (pinfunction "1_1") (pintype "passive"))
      (node (ref "R8") (pin "1") (pinfunction "1_1") (pintype "passive"))
      (node (ref "R83") (pin "1") (pinfunction "1_1") (pintype "passive"))
      (node (ref "R88") (pin "2") (pinfunction "2_2") (pintype "passive"))
      (node (ref "R95") (pin "1") (pinfunction "1_1") (pintype "passive"))
      (node (ref "T16") (pin "1") (pinfunction "1_1") (pintype "passive"))
      (node (ref "T25") (pin "1") (pinfunction "1_1") (pintype "passive"))
      (node (ref "T34") (pin "1") (pinfunction "1_1") (pintype "passive"))
      (node (ref "T6") (pin "1") (pinfunction "1_1") (pintype "passive"))
      (node (ref "U10") (pin "4") (pinfunction "VCC_4") (pintype "passive"))
      (node (ref "U10") (pin "6") (pinfunction "VCC_6") (pintype "passive"))
      (node (ref "U15") (pin "4") (pinfunction "VCC_4") (pintype "passive"))
      (node (ref "U15") (pin "6") (pinfunction "VCC_6") (pintype "passive"))
      (node (ref "U2") (pin "4") (pinfunction "VCC_4") (pintype "passive"))
      (node (ref "U2") (pin "6") (pinfunction "VCC_6") (pintype "passive"))
      (node (ref "U6") (pin "4") (pinfunction "VCC_4") (pintype "passive"))
      (node (ref "U6") (pin "6") (pinfunction "VCC_6") (pintype "passive"))
    )
    (net (code "3") (name "/A_A+") (class "Default")
      (node (ref "Q1") (pin "5") (pinfunction "B2_5") (pintype "passive"))
      (node (ref "U2") (pin "1") (pinfunction "PD3_1") (pintype "passive"))
    )
    (net (code "4") (name "/A_A-") (class "Default")
      (node (ref "R21") (pin "1") (pinfunction "1_1") (pintype "passive"))
      (node (ref "T8") (pin "1") (pinfunction "1_1") (pintype "passive"))
      (node (ref "U2") (pin "15") (pinfunction "PB3_15") (pintype "passive"))
    )
    (net (code "5") (name "/A_AN") (class "Default")
      (node (ref "R19") (pin "2") (pinfunction "2_2") (pintype "passive"))
      (node (ref "R21") (pin "2") (pinfunction "2_2") (pintype "passive"))
      (node (ref "U4") (pin "2") (pinfunction "G2_2") (pintype "passive"))
    )
    (net (code "6") (name "/A_AP") (class "Default")
      (node (ref "R11") (pin "2") (pinfunction "2_2") (pintype "passive"))
      (node (ref "R9") (pin "2") (pinfunction "2_2") (pintype "passive"))
      (node (ref "U4") (pin "4") (pinfunction "G1_4") (pintype "passive"))
    )
    (net (code "7") (name "/A_B+") (class "Default")
      (node (ref "Q1") (pin "2") (pinfunction "B1_2") (pintype "passive"))
      (node (ref "U2") (pin "2") (pinfunction "PD4_2") (pintype "passive"))
    )
    (net (code "8") (name "/A_B-") (class "Default")
      (node (ref "R10") (pin "1") (pinfunction "1_1") (pintype "passive"))
      (node (ref "U2") (pin "14") (pinfunction "PB2_14") (pintype "passive"))
    )
    (net (code "9") (name "/A_BN") (class "Default")
      (node (ref "R10") (pin "2") (pinfunction "2_2") (pintype "passive"))
      (node (ref "R23") (pin "2") (pinfunction "2_2") (pintype "passive"))
      (node (ref "U3") (pin "2") (pinfunction "G2_2") (pintype "passive"))
    )
    (net (code "10") (name "/A_BP") (class "Default")
      (node (ref "R3") (pin "2") (pinfunction "2_2") (pintype "passive"))
      (node (ref "R4") (pin "2") (pinfunction "2_2") (pintype "passive"))
      (node (ref "U3") (pin "4") (pinfunction "G1_4") (pintype "passive"))
    )
    (net (code "11") (name "/A_C+") (class "Default")
      (node (ref "Q2") (pin "2") (pinfunction "B1_2") (pintype "passive"))
      (node (ref "U2") (pin "9") (pinfunction "PD5_9") (pintype "passive"))
    )
    (net (code "12") (name "/A_C-") (class "Default")
      (node (ref "R2") (pin "1") (pinfunction "1_1") (pintype "passive"))
      (node (ref "U2") (pin "13") (pinfunction "PB1_13") (pintype "passive"))
    )
    (net (code "13") (name "/A_CN") (class "Default")
      (node (ref "R2") (pin "2") (pinfunction "2_2") (pintype "passive"))
      (node (ref "R24") (pin "2") (pinfunction "2_2") (pintype "passive"))
      (node (ref "U1") (pin "2") (pinfunction "G2_2") (pintype "passive"))
    )
    (net (code "14") (name "/A_CP") (class "Default")
      (node (ref "R22") (pin "2") (pinfunction "2_2") (pintype "passive"))
      (node (ref "R25") (pin "2") (pinfunction "2_2") (pintype "passive"))
      (node (ref "U1") (pin "4") (pinfunction "G1_4") (pintype "passive"))
    )
    (net (code "15") (name "/A_EMUA") (class "Default")
      (node (ref "R12") (pin "1") (pinfunction "1_1") (pintype "passive"))
      (node (ref "R15") (pin "1") (pinfunction "1_1") (pintype "passive"))
      (node (ref "R5") (pin "2") (pinfunction "2_2") (pintype "passive"))
      (node (ref "U2") (pin "28") (pinfunction "PC5_28") (pintype "passive"))
    )
    (net (code "16") (name "/A_EMUB") (class "Default")
      (node (ref "R13") (pin "1") (pinfunction "1_1") (pintype "passive"))
      (node (ref "R16") (pin "1") (pinfunction "1_1") (pintype "passive"))
      (node (ref "R6") (pin "2") (pinfunction "2_2") (pintype "passive"))
      (node (ref "U2") (pin "27") (pinfunction "PC4_27") (pintype "passive"))
    )
    (net (code "17") (name "/A_EMUC") (class "Default")
      (node (ref "R17") (pin "1") (pinfunction "1_1") (pintype "passive"))
      (node (ref "R18") (pin "1") (pinfunction "1_1") (pintype "passive"))
      (node (ref "R7") (pin "2") (pinfunction "2_2") (pintype "passive"))
      (node (ref "U2") (pin "11") (pinfunction "PD7_11") (pintype "passive"))
    )
    (net (code "18") (name "/A_MOTA") (class "Default")
      (node (ref "J1") (pin "3") (pinfunction "3_3") (pintype "passive"))
      (node (ref "R5") (pin "1") (pinfunction "1_1") (pintype "passive"))
      (node (ref "T7") (pin "1") (pinfunction "1_1") (pintype "passive"))
      (node (ref "U4") (pin "5") (pinfunction "D1_5") (pintype "passive"))
      (node (ref "U4") (pin "6") (pinfunction "D1_6") (pintype "passive"))
      (node (ref "U4") (pin "7") (pinfunction "D2_7") (pintype "passive"))
      (node (ref "U4") (pin "8") (pinfunction "D2_8") (pintype "passive"))
    )
    (net (code "19") (name "/A_MOTB") (class "Default")
      (node (ref "J1") (pin "2") (pinfunction "2_2") (pintype "passive"))
      (node (ref "R6") (pin "1") (pinfunction "1_1") (pintype "passive"))
      (node (ref "T4") (pin "1") (pinfunction "1_1") (pintype "passive"))
      (node (ref "U3") (pin "5") (pinfunction "D1_5") (pintype "passive"))
      (node (ref "U3") (pin "6") (pinfunction "D1_6") (pintype "passive"))
      (node (ref "U3") (pin "7") (pinfunction "D2_7") (pintype "passive"))
      (node (ref "U3") (pin "8") (pinfunction "D2_8") (pintype "passive"))
    )
    (net (code "20") (name "/A_MOTC") (class "Default")
      (node (ref "J1") (pin "1") (pinfunction "1_1") (pintype "passive"))
      (node (ref "R7") (pin "1") (pinfunction "1_1") (pintype "passive"))
      (node (ref "T1") (pin "1") (pinfunction "1_1") (pintype "passive"))
      (node (ref "U1") (pin "5") (pinfunction "D1_5") (pintype "passive"))
      (node (ref "U1") (pin "6") (pinfunction "D1_6") (pintype "passive"))
      (node (ref "U1") (pin "7") (pinfunction "D2_7") (pintype "passive"))
      (node (ref "U1") (pin "8") (pinfunction "D2_8") (pintype "passive"))
    )
    (net (code "21") (name "/A_STAR") (class "Default")
      (node (ref "R12") (pin "2") (pinfunction "2_2") (pintype "passive"))
      (node (ref "R13") (pin "2") (pinfunction "2_2") (pintype "passive"))
      (node (ref "R18") (pin "2") (pinfunction "2_2") (pintype "passive"))
      (node (ref "U2") (pin "10") (pinfunction "PD6_10") (pintype "passive"))
    )
    (net (code "22") (name "/B_A+") (class "Default")
      (node (ref "Q2") (pin "5") (pinfunction "B2_5") (pintype "passive"))
      (node (ref "U6") (pin "1") (pinfunction "PD3_1") (pintype "passive"))
    )
    (net (code "23") (name "/B_A-") (class "Default")
      (node (ref "R45") (pin "1") (pinfunction "1_1") (pintype "passive"))
      (node (ref "T17") (pin "1") (pinfunction "1_1") (pintype "passive"))
      (node (ref "U6") (pin "15") (pinfunction "PB3_15") (pintype "passive"))
    )
    (net (code "24") (name "/B_AN") (class "Default")
      (node (ref "R45") (pin "2") (pinfunction "2_2") (pintype "passive"))
      (node (ref "R52") (pin "2") (pinfunction "2_2") (pintype "passive"))
      (node (ref "U8") (pin "2") (pinfunction "G2_2") (pintype "passive"))
    )
    (net (code "25") (name "/B_AP") (class "Default")
      (node (ref "R27") (pin "2") (pinfunction "2_2") (pintype "passive"))
      (node (ref "R29") (pin "2") (pinfunction "2_2") (pintype "passive"))
      (node (ref "U8") (pin "4") (pinfunction "G1_4") (pintype "passive"))
    )
    (net (code "26") (name "/B_B+") (class "Default")
      (node (ref "Q3") (pin "2") (pinfunction "B1_2") (pintype "passive"))
      (node (ref "U6") (pin "2") (pinfunction "PD4_2") (pintype "passive"))
    )
    (net (code "27") (name "/B_B-") (class "Default")
      (node (ref "R31") (pin "1") (pinfunction "1_1") (pintype "passive"))
      (node (ref "U6") (pin "14") (pinfunction "PB2_14") (pintype "passive"))
    )
    (net (code "28") (name "/B_BN") (class "Default")
      (node (ref "R31") (pin "2") (pinfunction "2_2") (pintype "passive"))
      (node (ref "R54") (pin "2") (pinfunction "2_2") (pintype "passive"))
      (node (ref "U7") (pin "2") (pinfunction "G2_2") (pintype "passive"))
    )
    (net (code "29") (name "/B_BP") (class "Default")
      (node (ref "R30") (pin "2") (pinfunction "2_2") (pintype "passive"))
      (node (ref "R36") (pin "2") (pinfunction "2_2") (pintype "passive"))
      (node (ref "U7") (pin "4") (pinfunction "G1_4") (pintype "passive"))
    )
    (net (code "30") (name "/B_C+") (class "Default")
      (node (ref "Q3") (pin "5") (pinfunction "B2_5") (pintype "passive"))
      (node (ref "U6") (pin "9") (pinfunction "PD5_9") (pintype "passive"))
    )
    (net (code "31") (name "/B_C-") (class "Default")
      (node (ref "R28") (pin "1") (pinfunction "1_1") (pintype "passive"))
      (node (ref "U6") (pin "13") (pinfunction "PB1_13") (pintype "passive"))
    )
    (net (code "32") (name "/B_CN") (class "Default")
      (node (ref "R28") (pin "2") (pinfunction "2_2") (pintype "passive"))
      (node (ref "R55") (pin "2") (pinfunction "2_2") (pintype "passive"))
      (node (ref "U5") (pin "2") (pinfunction "G2_2") (pintype "passive"))
    )
    (net (code "33") (name "/B_CP") (class "Default")
      (node (ref "R41") (pin "2") (pinfunction "2_2") (pintype "passive"))
      (node (ref "R44") (pin "2") (pinfunction "2_2") (pintype "passive"))
      (node (ref "U5") (pin "4") (pinfunction "G1_4") (pintype "passive"))
    )
    (net (code "34") (name "/B_EMUA") (class "Default")
      (node (ref "R32") (pin "2") (pinfunction "2_2") (pintype "passive"))
      (node (ref "R42") (pin "1") (pinfunction "1_1") (pintype "passive"))
      (node (ref "R47") (pin "1") (pinfunction "1_1") (pintype "passive"))
      (node (ref "U6") (pin "28") (pinfunction "PC5_28") (pintype "passive"))
    )
    (net (code "35") (name "/B_EMUB") (class "Default")
      (node (ref "R33") (pin "2") (pinfunction "2_2") (pintype "passive"))
      (node (ref "R43") (pin "1") (pinfunction "1_1") (pintype "passive"))
      (node (ref "R48") (pin "1") (pinfunction "1_1") (pintype "passive"))
      (node (ref "U6") (pin "27") (pinfunction "PC4_27") (pintype "passive"))
    )
    (net (code "36") (name "/B_EMUC") (class "Default")
      (node (ref "R34") (pin "2") (pinfunction "2_2") (pintype "passive"))
      (node (ref "R49") (pin "1") (pinfunction "1_1") (pintype "passive"))
      (node (ref "R50") (pin "1") (pinfunction "1_1") (pintype "passive"))
      (node (ref "U6") (pin "11") (pinfunction "PD7_11") (pintype "passive"))
    )
    (net (code "37") (name "/B_MOTA") (class "Default")
      (node (ref "J3") (pin "3") (pinfunction "3_3") (pintype "passive"))
      (node (ref "J3") (pin "4") (pinfunction "4_4") (pintype "passive"))
      (node (ref "R32") (pin "1") (pinfunction "1_1") (pintype "passive"))
      (node (ref "T12") (pin "1") (pinfunction "1_1") (pintype "passive"))
      (node (ref "U8") (pin "5") (pinfunction "D1_5") (pintype "passive"))
      (node (ref "U8") (pin "6") (pinfunction "D1_6") (pintype "passive"))
      (node (ref "U8") (pin "7") (pinfunction "D2_7") (pintype "passive"))
      (node (ref "U8") (pin "8") (pinfunction "D2_8") (pintype "passive"))
    )
    (net (code "38") (name "/B_MOTB") (class "Default")
      (node (ref "J3") (pin "2") (pinfunction "2_2") (pintype "passive"))
      (node (ref "R33") (pin "1") (pinfunction "1_1") (pintype "passive"))
      (node (ref "T11") (pin "1") (pinfunction "1_1") (pintype "passive"))
      (node (ref "U7") (pin "5") (pinfunction "D1_5") (pintype "passive"))
      (node (ref "U7") (pin "6") (pinfunction "D1_6") (pintype "passive"))
      (node (ref "U7") (pin "7") (pinfunction "D2_7") (pintype "passive"))
      (node (ref "U7") (pin "8") (pinfunction "D2_8") (pintype "passive"))
    )
    (net (code "39") (name "/B_MOTC") (class "Default")
      (node (ref "J3") (pin "1") (pinfunction "1_1") (pintype "passive"))
      (node (ref "R34") (pin "1") (pinfunction "1_1") (pintype "passive"))
      (node (ref "T10") (pin "1") (pinfunction "1_1") (pintype "passive"))
      (node (ref "U5") (pin "5") (pinfunction "D1_5") (pintype "passive"))
      (node (ref "U5") (pin "6") (pinfunction "D1_6") (pintype "passive"))
      (node (ref "U5") (pin "7") (pinfunction "D2_7") (pintype "passive"))
      (node (ref "U5") (pin "8") (pinfunction "D2_8") (pintype "passive"))
    )
    (net (code "40") (name "/B_STAR") (class "Default")
      (node (ref "R42") (pin "2") (pinfunction "2_2") (pintype "passive"))
      (node (ref "R43") (pin "2") (pinfunction "2_2") (pintype "passive"))
      (node (ref "R50") (pin "2") (pinfunction "2_2") (pintype "passive"))
      (node (ref "U6") (pin "10") (pinfunction "PD6_10") (pintype "passive"))
    )
    (net (code "41") (name "/CAN2_RX{slash}USART5_RX_ESC") (class "Default")
      (node (ref "Q7") (pin "3") (pinfunction "C_3") (pintype "passive"))
      (node (ref "R57") (pin "1") (pinfunction "1_1") (pintype "passive"))
    )
    (net (code "42") (name "/CAN2_TX{slash}USART5_TX_ESC") (class "Default")
      (node (ref "Q5") (pin "1") (pinfunction "B_1") (pintype "passive"))
      (node (ref "R46") (pin "2") (pinfunction "2_2") (pintype "passive"))
    )
    (net (code "43") (name "/C_A+") (class "Default")
      (node (ref "Q6") (pin "5") (pinfunction "B2_5") (pintype "passive"))
      (node (ref "U10") (pin "1") (pinfunction "PD3_1") (pintype "passive"))
    )
    (net (code "44") (name "/C_A-") (class "Default")
      (node (ref "R79") (pin "1") (pinfunction "1_1") (pintype "passive"))
      (node (ref "T26") (pin "1") (pinfunction "1_1") (pintype "passive"))
      (node (ref "U10") (pin "15") (pinfunction "PB3_15") (pintype "passive"))
    )
    (net (code "45") (name "/C_AN") (class "Default")
      (node (ref "R78") (pin "2") (pinfunction "2_2") (pintype "passive"))
      (node (ref "R79") (pin "2") (pinfunction "2_2") (pintype "passive"))
      (node (ref "U12") (pin "2") (pinfunction "G2_2") (pintype "passive"))
    )
    (net (code "46") (name "/C_AP") (class "Default")
      (node (ref "R67") (pin "2") (pinfunction "2_2") (pintype "passive"))
      (node (ref "R70") (pin "2") (pinfunction "2_2") (pintype "passive"))
      (node (ref "U12") (pin "4") (pinfunction "G1_4") (pintype "passive"))
    )
    (net (code "47") (name "/C_B+") (class "Default")
      (node (ref "Q6") (pin "2") (pinfunction "B1_2") (pintype "passive"))
      (node (ref "U10") (pin "2") (pinfunction "PD4_2") (pintype "passive"))
    )
    (net (code "48") (name "/C_B-") (class "Default")
      (node (ref "R68") (pin "1") (pinfunction "1_1") (pintype "passive"))
      (node (ref "U10") (pin "14") (pinfunction "PB2_14") (pintype "passive"))
    )
    (net (code "49") (name "/C_BN") (class "Default")
      (node (ref "R68") (pin "2") (pinfunction "2_2") (pintype "passive"))
      (node (ref "R81") (pin "2") (pinfunction "2_2") (pintype "passive"))
      (node (ref "U11") (pin "2") (pinfunction "G2_2") (pintype "passive"))
    )
    (net (code "50") (name "/C_BP") (class "Default")
      (node (ref "R59") (pin "2") (pinfunction "2_2") (pintype "passive"))
      (node (ref "R61") (pin "2") (pinfunction "2_2") (pintype "passive"))
      (node (ref "U11") (pin "4") (pinfunction "G1_4") (pintype "passive"))
    )
    (net (code "51") (name "/C_C+") (class "Default")
      (node (ref "Q9") (pin "2") (pinfunction "B1_2") (pintype "passive"))
      (node (ref "U10") (pin "9") (pinfunction "PD5_9") (pintype "passive"))
    )
    (net (code "52") (name "/C_C-") (class "Default")
      (node (ref "R58") (pin "1") (pinfunction "1_1") (pintype "passive"))
      (node (ref "U10") (pin "13") (pinfunction "PB1_13") (pintype "passive"))
    )
    (net (code "53") (name "/C_CN") (class "Default")
      (node (ref "R58") (pin "2") (pinfunction "2_2") (pintype "passive"))
      (node (ref "R84") (pin "2") (pinfunction "2_2") (pintype "passive"))
      (node (ref "U9") (pin "2") (pinfunction "G2_2") (pintype "passive"))
    )
    (net (code "54") (name "/C_CP") (class "Default")
      (node (ref "R82") (pin "2") (pinfunction "2_2") (pintype "passive"))
      (node (ref "R85") (pin "2") (pinfunction "2_2") (pintype "passive"))
      (node (ref "U9") (pin "4") (pinfunction "G1_4") (pintype "passive"))
    )
    (net (code "55") (name "/C_EMUA") (class "Default")
      (node (ref "R63") (pin "2") (pinfunction "2_2") (pintype "passive"))
      (node (ref "R72") (pin "1") (pinfunction "1_1") (pintype "passive"))
      (node (ref "R74") (pin "1") (pinfunction "1_1") (pintype "passive"))
      (node (ref "U10") (pin "28") (pinfunction "PC5_28") (pintype "passive"))
    )
    (net (code "56") (name "/C_EMUB") (class "Default")
      (node (ref "R64") (pin "2") (pinfunction "2_2") (pintype "passive"))
      (node (ref "R73") (pin "1") (pinfunction "1_1") (pintype "passive"))
      (node (ref "R75") (pin "1") (pinfunction "1_1") (pintype "passive"))
      (node (ref "U10") (pin "27") (pinfunction "PC4_27") (pintype "passive"))
    )
    (net (code "57") (name "/C_EMUC") (class "Default")
      (node (ref "R65") (pin "2") (pinfunction "2_2") (pintype "passive"))
      (node (ref "R76") (pin "1") (pinfunction "1_1") (pintype "passive"))
      (node (ref "R77") (pin "1") (pinfunction "1_1") (pintype "passive"))
      (node (ref "U10") (pin "11") (pinfunction "PD7_11") (pintype "passive"))
    )
    (net (code "58") (name "/C_MOTA") (class "Default")
      (node (ref "J5") (pin "3") (pinfunction "3_3") (pintype "passive"))
      (node (ref "R63") (pin "1") (pinfunction "1_1") (pintype "passive"))
      (node (ref "T23") (pin "1") (pinfunction "1_1") (pintype "passive"))
      (node (ref "U12") (pin "5") (pinfunction "D1_5") (pintype "passive"))
      (node (ref "U12") (pin "6") (pinfunction "D1_6") (pintype "passive"))
      (node (ref "U12") (pin "7") (pinfunction "D2_7") (pintype "passive"))
      (node (ref "U12") (pin "8") (pinfunction "D2_8") (pintype "passive"))
    )
    (net (code "59") (name "/C_MOTB") (class "Default")
      (node (ref "J5") (pin "2") (pinfunction "2_2") (pintype "passive"))
      (node (ref "R64") (pin "1") (pinfunction "1_1") (pintype "passive"))
      (node (ref "T20") (pin "1") (pinfunction "1_1") (pintype "passive"))
      (node (ref "U11") (pin "5") (pinfunction "D1_5") (pintype "passive"))
      (node (ref "U11") (pin "6") (pinfunction "D1_6") (pintype "passive"))
      (node (ref "U11") (pin "7") (pinfunction "D2_7") (pintype "passive"))
      (node (ref "U11") (pin "8") (pinfunction "D2_8") (pintype "passive"))
    )
    (net (code "60") (name "/C_MOTC") (class "Default")
      (node (ref "J5") (pin "1") (pinfunction "1_1") (pintype "passive"))
      (node (ref "J5") (pin "5") (pinfunction "5_5") (pintype "passive"))
      (node (ref "R65") (pin "1") (pinfunction "1_1") (pintype "passive"))
      (node (ref "T19") (pin "1") (pinfunction "1_1") (pintype "passive"))
      (node (ref "U9") (pin "5") (pinfunction "D1_5") (pintype "passive"))
      (node (ref "U9") (pin "6") (pinfunction "D1_6") (pintype "passive"))
      (node (ref "U9") (pin "7") (pinfunction "D2_7") (pintype "passive"))
      (node (ref "U9") (pin "8") (pinfunction "D2_8") (pintype "passive"))
    )
    (net (code "61") (name "/C_STAR") (class "Default")
      (node (ref "R72") (pin "2") (pinfunction "2_2") (pintype "passive"))
      (node (ref "R73") (pin "2") (pinfunction "2_2") (pintype "passive"))
      (node (ref "R77") (pin "2") (pinfunction "2_2") (pintype "passive"))
      (node (ref "U10") (pin "10") (pinfunction "PD6_10") (pintype "passive"))
    )
    (net (code "62") (name "/D_A+") (class "Default")
      (node (ref "Q9") (pin "5") (pinfunction "B2_5") (pintype "passive"))
      (node (ref "U15") (pin "1") (pinfunction "PD3_1") (pintype "passive"))
    )
    (net (code "63") (name "/D_A-") (class "Default")
      (node (ref "R98") (pin "1") (pinfunction "1_1") (pintype "passive"))
      (node (ref "T35") (pin "1") (pinfunction "1_1") (pintype "passive"))
      (node (ref "U15") (pin "15") (pinfunction "PB3_15") (pintype "passive"))
    )
    (net (code "64") (name "/D_AN") (class "Default")
      (node (ref "R105") (pin "2") (pinfunction "2_2") (pintype "passive"))
      (node (ref "R98") (pin "2") (pinfunction "2_2") (pintype "passive"))
      (node (ref "U16") (pin "2") (pinfunction "G2_2") (pintype "passive"))
    )
    (net (code "65") (name "/D_AP") (class "Default")
      (node (ref "R87") (pin "2") (pinfunction "2_2") (pintype "passive"))
      (node (ref "R89") (pin "2") (pinfunction "2_2") (pintype "passive"))
      (node (ref "U16") (pin "4") (pinfunction "G1_4") (pintype "passive"))
    )
    (net (code "66") (name "/D_B+") (class "Default")
      (node (ref "Q10") (pin "2") (pinfunction "B1_2") (pintype "passive"))
      (node (ref "U15") (pin "2") (pinfunction "PD4_2") (pintype "passive"))
    )
    (net (code "67") (name "/D_B-") (class "Default")
      (node (ref "R90") (pin "1") (pinfunction "1_1") (pintype "passive"))
      (node (ref "U15") (pin "14") (pinfunction "PB2_14") (pintype "passive"))
    )
    (net (code "68") (name "/D_BN") (class "Default")
      (node (ref "R108") (pin "2") (pinfunction "2_2") (pintype "passive"))
      (node (ref "R90") (pin "2") (pinfunction "2_2") (pintype "passive"))
      (node (ref "U14") (pin "2") (pinfunction "G2_2") (pintype "passive"))
    )
    (net (code "69") (name "/D_BP") (class "Default")
      (node (ref "R94") (pin "2") (pinfunction "2_2") (pintype "passive"))
      (node (ref "R96") (pin "2") (pinfunction "2_2") (pintype "passive"))
      (node (ref "U14") (pin "4") (pinfunction "G1_4") (pintype "passive"))
    )
    (net (code "70") (name "/D_C+") (class "Default")
      (node (ref "Q10") (pin "5") (pinfunction "B2_5") (pintype "passive"))
      (node (ref "U15") (pin "9") (pinfunction "PD5_9") (pintype "passive"))
    )
    (net (code "71") (name "/D_C-") (class "Default")
      (node (ref "R86") (pin "1") (pinfunction "1_1") (pintype "passive"))
      (node (ref "U15") (pin "13") (pinfunction "PB1_13") (pintype "passive"))
    )
    (net (code "72") (name "/D_CN") (class "Default")
      (node (ref "R110") (pin "2") (pinfunction "2_2") (pintype "passive"))
      (node (ref "R86") (pin "2") (pinfunction "2_2") (pintype "passive"))
      (node (ref "U13") (pin "2") (pinfunction "G2_2") (pintype "passive"))
    )
    (net (code "73") (name "/D_CP") (class "Default")
      (node (ref "R104") (pin "2") (pinfunction "2_2") (pintype "passive"))
      (node (ref "R107") (pin "2") (pinfunction "2_2") (pintype "passive"))
      (node (ref "U13") (pin "4") (pinfunction "G1_4") (pintype "passive"))
    )
    (net (code "74") (name "/D_EMUA") (class "Default")
      (node (ref "R100") (pin "1") (pinfunction "1_1") (pintype "passive"))
      (node (ref "R91") (pin "2") (pinfunction "2_2") (pintype "passive"))
      (node (ref "R97") (pin "1") (pinfunction "1_1") (pintype "passive"))
      (node (ref "U15") (pin "28") (pinfunction "PC5_28") (pintype "passive"))
    )
    (net (code "75") (name "/D_EMUB") (class "Default")
      (node (ref "R101") (pin "1") (pinfunction "1_1") (pintype "passive"))
      (node (ref "R92") (pin "2") (pinfunction "2_2") (pintype "passive"))
      (node (ref "R99") (pin "1") (pinfunction "1_1") (pintype "passive"))
      (node (ref "U15") (pin "27") (pinfunction "PC4_27") (pintype "passive"))
    )
    (net (code "76") (name "/D_EMUC") (class "Default")
      (node (ref "R102") (pin "1") (pinfunction "1_1") (pintype "passive"))
      (node (ref "R103") (pin "1") (pinfunction "1_1") (pintype "passive"))
      (node (ref "R93") (pin "2") (pinfunction "2_2") (pintype "passive"))
      (node (ref "U15") (pin "11") (pinfunction "PD7_11") (pintype "passive"))
    )
    (net (code "77") (name "/D_MOTA") (class "Default")
      (node (ref "J6") (pin "3") (pinfunction "3_3") (pintype "passive"))
      (node (ref "R91") (pin "1") (pinfunction "1_1") (pintype "passive"))
      (node (ref "T30") (pin "1") (pinfunction "1_1") (pintype "passive"))
      (node (ref "U16") (pin "5") (pinfunction "D1_5") (pintype "passive"))
      (node (ref "U16") (pin "6") (pinfunction "D1_6") (pintype "passive"))
      (node (ref "U16") (pin "7") (pinfunction "D2_7") (pintype "passive"))
      (node (ref "U16") (pin "8") (pinfunction "D2_8") (pintype "passive"))
    )
    (net (code "78") (name "/D_MOTB") (class "Default")
      (node (ref "J6") (pin "2") (pinfunction "2_2") (pintype "passive"))
      (node (ref "R92") (pin "1") (pinfunction "1_1") (pintype "passive"))
      (node (ref "T29") (pin "1") (pinfunction "1_1") (pintype "passive"))
      (node (ref "U14") (pin "5") (pinfunction "D1_5") (pintype "passive"))
      (node (ref "U14") (pin "6") (pinfunction "D1_6") (pintype "passive"))
      (node (ref "U14") (pin "7") (pinfunction "D2_7") (pintype "passive"))
      (node (ref "U14") (pin "8") (pinfunction "D2_8") (pintype "passive"))
    )
    (net (code "79") (name "/D_MOTC") (class "Default")
      (node (ref "J6") (pin "1") (pinfunction "1_1") (pintype "passive"))
      (node (ref "R93") (pin "1") (pinfunction "1_1") (pintype "passive"))
      (node (ref "T28") (pin "1") (pinfunction "1_1") (pintype "passive"))
      (node (ref "U13") (pin "5") (pinfunction "D1_5") (pintype "passive"))
      (node (ref "U13") (pin "6") (pinfunction "D1_6") (pintype "passive"))
      (node (ref "U13") (pin "7") (pinfunction "D2_7") (pintype "passive"))
      (node (ref "U13") (pin "8") (pinfunction "D2_8") (pintype "passive"))
    )
    (net (code "80") (name "/D_STAR") (class "Default")
      (node (ref "R103") (pin "2") (pinfunction "2_2") (pintype "passive"))
      (node (ref "R97") (pin "2") (pinfunction "2_2") (pintype "passive"))
      (node (ref "R99") (pin "2") (pinfunction "2_2") (pintype "passive"))
      (node (ref "U15") (pin "10") (pinfunction "PD6_10") (pintype "passive"))
    )
    (net (code "81") (name "/ESC-RX") (class "Default")
      (node (ref "J2") (pin "1") (pinfunction "1_1") (pintype "passive"))
      (node (ref "R37") (pin "1") (pinfunction "1_1") (pintype "passive"))
      (node (ref "U10") (pin "30") (pinfunction "PD0_30") (pintype "passive"))
      (node (ref "U15") (pin "30") (pinfunction "PD0_30") (pintype "passive"))
      (node (ref "U2") (pin "30") (pinfunction "PD0_30") (pintype "passive"))
      (node (ref "U6") (pin "30") (pinfunction "PD0_30") (pintype "passive"))
    )
    (net (code "82") (name "/ESC-TX") (class "Default")
      (node (ref "J4") (pin "1") (pinfunction "1_1") (pintype "passive"))
      (node (ref "R66") (pin "1") (pinfunction "1_1") (pintype "passive"))
      (node (ref "U10") (pin "31") (pinfunction "PD1_31") (pintype "passive"))
      (node (ref "U15") (pin "31") (pinfunction "PD1_31") (pintype "passive"))
      (node (ref "U2") (pin "31") (pinfunction "PD1_31") (pintype "passive"))
      (node (ref "U6") (pin "31") (pinfunction "PD1_31") (pintype "passive"))
    )
    (net (code "83") (name "/RESET_A") (class "Default")
      (node (ref "R1") (pin "1") (pinfunction "1_1") (pintype "passive"))
      (node (ref "T3") (pin "1") (pinfunction "1_1") (pintype "passive"))
      (node (ref "U2") (pin "29") (pinfunction "PC6_29") (pintype "passive"))
    )
    (net (code "84") (name "/RESET_B") (class "Default")
      (node (ref "R26") (pin "1") (pinfunction "1_1") (pintype "passive"))
      (node (ref "T14") (pin "1") (pinfunction "1_1") (pintype "passive"))
      (node (ref "U6") (pin "29") (pinfunction "PC6_29") (pintype "passive"))
    )
    (net (code "85") (name "/RESET_C") (class "Default")
      (node (ref "R56") (pin "1") (pinfunction "1_1") (pintype "passive"))
      (node (ref "T22") (pin "1") (pinfunction "1_1") (pintype "passive"))
      (node (ref "U10") (pin "29") (pinfunction "PC6_29") (pintype "passive"))
    )
    (net (code "86") (name "/RESET_D") (class "Default")
      (node (ref "R88") (pin "1") (pinfunction "1_1") (pintype "passive"))
      (node (ref "T32") (pin "1") (pinfunction "1_1") (pintype "passive"))
      (node (ref "U15") (pin "29") (pinfunction "PC6_29") (pintype "passive"))
    )
    (net (code "87") (name "GND") (class "Default")
      (node (ref "C1") (pin "2") (pinfunction "2_2") (pintype "passive"))
      (node (ref "C10") (pin "2") (pinfunction "2_2") (pintype "passive"))
      (node (ref "C11") (pin "2") (pinfunction "2_2") (pintype "passive"))
      (node (ref "C12") (pin "2") (pinfunction "2_2") (pintype "passive"))
      (node (ref "C13") (pin "2") (pinfunction "2_2") (pintype "passive"))
      (node (ref "C14") (pin "2") (pinfunction "2_2") (pintype "passive"))
      (node (ref "C15") (pin "2") (pinfunction "2_2") (pintype "passive"))
      (node (ref "C16") (pin "2") (pinfunction "2_2") (pintype "passive"))
      (node (ref "C17") (pin "2") (pinfunction "2_2") (pintype "passive"))
      (node (ref "C18") (pin "2") (pinfunction "2_2") (pintype "passive"))
      (node (ref "C19") (pin "2") (pinfunction "2_2") (pintype "passive"))
      (node (ref "C2") (pin "2") (pinfunction "2_2") (pintype "passive"))
      (node (ref "C20") (pin "2") (pinfunction "2_2") (pintype "passive"))
      (node (ref "C21") (pin "2") (pinfunction "2_2") (pintype "passive"))
      (node (ref "C22") (pin "2") (pinfunction "2_2") (pintype "passive"))
      (node (ref "C23") (pin "2") (pinfunction "2_2") (pintype "passive"))
      (node (ref "C24") (pin "2") (pinfunction "2_2") (pintype "passive"))
      (node (ref "C25") (pin "2") (pinfunction "2_2") (pintype "passive"))
      (node (ref "C26") (pin "2") (pinfunction "2_2") (pintype "passive"))
      (node (ref "C27") (pin "2") (pinfunction "2_2") (pintype "passive"))
      (node (ref "C28") (pin "2") (pinfunction "2_2") (pintype "passive"))
      (node (ref "C29") (pin "2") (pinfunction "2_2") (pintype "passive"))
      (node (ref "C3") (pin "2") (pinfunction "2_2") (pintype "passive"))
      (node (ref "C30") (pin "2") (pinfunction "2_2") (pintype "passive"))
      (node (ref "C31") (pin "2") (pinfunction "2_2") (pintype "passive"))
      (node (ref "C32") (pin "2") (pinfunction "2_2") (pintype "passive"))
      (node (ref "C33") (pin "2") (pinfunction "2_2") (pintype "passive"))
      (node (ref "C34") (pin "2") (pinfunction "2_2") (pintype "passive"))
      (node (ref "C35") (pin "2") (pinfunction "2_2") (pintype "passive"))
      (node (ref "C36") (pin "2") (pinfunction "2_2") (pintype "passive"))
      (node (ref "C37") (pin "2") (pinfunction "2_2") (pintype "passive"))
      (node (ref "C38") (pin "2") (pinfunction "2_2") (pintype "passive"))
      (node (ref "C39") (pin "2") (pinfunction "2_2") (pintype "passive"))
      (node (ref "C4") (pin "2") (pinfunction "2_2") (pintype "passive"))
      (node (ref "C40") (pin "2") (pinfunction "2_2") (pintype "passive"))
      (node (ref "C41") (pin "2") (pinfunction "2_2") (pintype "passive"))
      (node (ref "C42") (pin "2") (pinfunction "2_2") (pintype "passive"))
      (node (ref "C43") (pin "2") (pinfunction "2_2") (pintype "passive"))
      (node (ref "C44") (pin "2") (pinfunction "2_2") (pintype "passive"))
      (node (ref "C45") (pin "2") (pinfunction "2_2") (pintype "passive"))
      (node (ref "C46") (pin "2") (pinfunction "2_2") (pintype "passive"))
      (node (ref "C47") (pin "2") (pinfunction "2_2") (pintype "passive"))
      (node (ref "C48") (pin "2") (pinfunction "2_2") (pintype "passive"))
      (node (ref "C5") (pin "2") (pinfunction "2_2") (pintype "passive"))
      (node (ref "C6") (pin "2") (pinfunction "2_2") (pintype "passive"))
      (node (ref "C7") (pin "2") (pinfunction "2_2") (pintype "passive"))
      (node (ref "C8") (pin "2") (pinfunction "2_2") (pintype "passive"))
      (node (ref "C9") (pin "2") (pinfunction "2_2") (pintype "passive"))
      (node (ref "J1") (pin "4") (pinfunction "4_4") (pintype "passive"))
      (node (ref "J1") (pin "5") (pinfunction "5_5") (pintype "passive"))
      (node (ref "J3") (pin "5") (pinfunction "5_5") (pintype "passive"))
      (node (ref "J5") (pin "4") (pinfunction "4_4") (pintype "passive"))
      (node (ref "J6") (pin "4") (pinfunction "4_4") (pintype "passive"))
      (node (ref "J6") (pin "5") (pinfunction "5_5") (pintype "passive"))
      (node (ref "Q1") (pin "1") (pinfunction "E1_1") (pintype "passive"))
      (node (ref "Q1") (pin "4") (pinfunction "E2_4") (pintype "passive"))
      (node (ref "Q10") (pin "1") (pinfunction "E1_1") (pintype "passive"))
      (node (ref "Q10") (pin "4") (pinfunction "E2_4") (pintype "passive"))
      (node (ref "Q2") (pin "1") (pinfunction "E1_1") (pintype "passive"))
      (node (ref "Q2") (pin "4") (pinfunction "E2_4") (pintype "passive"))
      (node (ref "Q3") (pin "1") (pinfunction "E1_1") (pintype "passive"))
      (node (ref "Q3") (pin "4") (pinfunction "E2_4") (pintype "passive"))
      (node (ref "Q4") (pin "2") (pinfunction "E_2") (pintype "passive"))
      (node (ref "Q5") (pin "2") (pinfunction "E_2") (pintype "passive"))
      (node (ref "Q6") (pin "1") (pinfunction "E1_1") (pintype "passive"))
      (node (ref "Q6") (pin "4") (pinfunction "E2_4") (pintype "passive"))
      (node (ref "Q7") (pin "2") (pinfunction "E_2") (pintype "passive"))
      (node (ref "Q8") (pin "2") (pinfunction "E_2") (pintype "passive"))
      (node (ref "Q9") (pin "1") (pinfunction "E1_1") (pintype "passive"))
      (node (ref "Q9") (pin "4") (pinfunction "E2_4") (pintype "passive"))
      (node (ref "R100") (pin "2") (pinfunction "2_2") (pintype "passive"))
      (node (ref "R101") (pin "2") (pinfunction "2_2") (pintype "passive"))
      (node (ref "R102") (pin "2") (pinfunction "2_2") (pintype "passive"))
      (node (ref "R105") (pin "1") (pinfunction "1_1") (pintype "passive"))
      (node (ref "R108") (pin "1") (pinfunction "1_1") (pintype "passive"))
      (node (ref "R110") (pin "1") (pinfunction "1_1") (pintype "passive"))
      (node (ref "R14") (pin "1") (pinfunction "1_1") (pintype "passive"))
      (node (ref "R15") (pin "2") (pinfunction "2_2") (pintype "passive"))
      (node (ref "R16") (pin "2") (pinfunction "2_2") (pintype "passive"))
      (node (ref "R17") (pin "2") (pinfunction "2_2") (pintype "passive"))
      (node (ref "R19") (pin "1") (pinfunction "1_1") (pintype "passive"))
      (node (ref "R20") (pin "1") (pinfunction "1_1") (pintype "passive"))
      (node (ref "R23") (pin "1") (pinfunction "1_1") (pintype "passive"))
      (node (ref "R24") (pin "1") (pinfunction "1_1") (pintype "passive"))
      (node (ref "R46") (pin "1") (pinfunction "1_1") (pintype "passive"))
      (node (ref "R47") (pin "2") (pinfunction "2_2") (pintype "passive"))
      (node (ref "R48") (pin "2") (pinfunction "2_2") (pintype "passive"))
      (node (ref "R49") (pin "2") (pinfunction "2_2") (pintype "passive"))
      (node (ref "R52") (pin "1") (pinfunction "1_1") (pintype "passive"))
      (node (ref "R53") (pin "1") (pinfunction "1_1") (pintype "passive"))
      (node (ref "R54") (pin "1") (pinfunction "1_1") (pintype "passive"))
      (node (ref "R55") (pin "1") (pinfunction "1_1") (pintype "passive"))
      (node (ref "R69") (pin "1") (pinfunction "1_1") (pintype "passive"))
      (node (ref "R74") (pin "2") (pinfunction "2_2") (pintype "passive"))
      (node (ref "R75") (pin "2") (pinfunction "2_2") (pintype "passive"))
      (node (ref "R76") (pin "2") (pinfunction "2_2") (pintype "passive"))
      (node (ref "R78") (pin "1") (pinfunction "1_1") (pintype "passive"))
      (node (ref "R80") (pin "1") (pinfunction "1_1") (pintype "passive"))
      (node (ref "R81") (pin "1") (pinfunction "1_1") (pintype "passive"))
      (node (ref "R84") (pin "1") (pinfunction "1_1") (pintype "passive"))
      (node (ref "T18") (pin "1") (pinfunction "1_1") (pintype "passive"))
      (node (ref "T27") (pin "1") (pinfunction "1_1") (pintype "passive"))
      (node (ref "T36") (pin "1") (pinfunction "1_1") (pintype "passive"))
      (node (ref "T9") (pin "1") (pinfunction "1_1") (pintype "passive"))
      (node (ref "U1") (pin "1") (pinfunction "S2_1") (pintype "passive"))
      (node (ref "U10") (pin "21") (pinfunction "GND_21") (pintype "passive"))
      (node (ref "U10") (pin "3") (pinfunction "GND_3") (pintype "passive"))
      (node (ref "U10") (pin "5") (pinfunction "GND_5") (pintype "passive"))
      (node (ref "U11") (pin "1") (pinfunction "S2_1") (pintype "passive"))
      (node (ref "U12") (pin "1") (pinfunction "S2_1") (pintype "passive"))
      (node (ref "U13") (pin "1") (pinfunction "S2_1") (pintype "passive"))
      (node (ref "U14") (pin "1") (pinfunction "S2_1") (pintype "passive"))
      (node (ref "U15") (pin "21") (pinfunction "GND_21") (pintype "passive"))
      (node (ref "U15") (pin "3") (pinfunction "GND_3") (pintype "passive"))
      (node (ref "U15") (pin "5") (pinfunction "GND_5") (pintype "passive"))
      (node (ref "U16") (pin "1") (pinfunction "S2_1") (pintype "passive"))
      (node (ref "U2") (pin "21") (pinfunction "GND_21") (pintype "passive"))
      (node (ref "U2") (pin "3") (pinfunction "GND_3") (pintype "passive"))
      (node (ref "U2") (pin "5") (pinfunction "GND_5") (pintype "passive"))
      (node (ref "U3") (pin "1") (pinfunction "S2_1") (pintype "passive"))
      (node (ref "U4") (pin "1") (pinfunction "S2_1") (pintype "passive"))
      (node (ref "U5") (pin "1") (pinfunction "S2_1") (pintype "passive"))
      (node (ref "U6") (pin "21") (pinfunction "GND_21") (pintype "passive"))
      (node (ref "U6") (pin "3") (pinfunction "GND_3") (pintype "passive"))
      (node (ref "U6") (pin "5") (pinfunction "GND_5") (pintype "passive"))
      (node (ref "U7") (pin "1") (pinfunction "S2_1") (pintype "passive"))
      (node (ref "U8") (pin "1") (pinfunction "S2_1") (pintype "passive"))
      (node (ref "U9") (pin "1") (pinfunction "S2_1") (pintype "passive"))
      (node (ref "X1") (pin "2") (pinfunction "G_2") (pintype "passive"))
      (node (ref "X1") (pin "4") (pinfunction "G_4") (pintype "passive"))
      (node (ref "X2") (pin "2") (pinfunction "G_2") (pintype "passive"))
      (node (ref "X2") (pin "4") (pinfunction "G_4") (pintype "passive"))
      (node (ref "X3") (pin "2") (pinfunction "G_2") (pintype "passive"))
      (node (ref "X3") (pin "4") (pinfunction "G_4") (pintype "passive"))
      (node (ref "X4") (pin "2") (pinfunction "G_2") (pintype "passive"))
      (node (ref "X4") (pin "4") (pinfunction "G_4") (pintype "passive"))
    )
    (net (code "88") (name "Net-(Q1-C1)") (class "Default")
      (node (ref "Q1") (pin "6") (pinfunction "C1_6") (pintype "passive"))
      (node (ref "R4") (pin "1") (pinfunction "1_1") (pintype "passive"))
    )
    (net (code "89") (name "Net-(Q1-C2)") (class "Default")
      (node (ref "Q1") (pin "3") (pinfunction "C2_3") (pintype "passive"))
      (node (ref "R11") (pin "1") (pinfunction "1_1") (pintype "passive"))
    )
    (net (code "90") (name "Net-(Q2-C1)") (class "Default")
      (node (ref "Q2") (pin "6") (pinfunction "C1_6") (pintype "passive"))
      (node (ref "R25") (pin "1") (pinfunction "1_1") (pintype "passive"))
    )
    (net (code "91") (name "Net-(Q2-C2)") (class "Default")
      (node (ref "Q2") (pin "3") (pinfunction "C2_3") (pintype "passive"))
      (node (ref "R29") (pin "1") (pinfunction "1_1") (pintype "passive"))
    )
    (net (code "92") (name "Net-(Q3-C1)") (class "Default")
      (node (ref "Q3") (pin "6") (pinfunction "C1_6") (pintype "passive"))
      (node (ref "R36") (pin "1") (pinfunction "1_1") (pintype "passive"))
    )
    (net (code "93") (name "Net-(Q3-C2)") (class "Default")
      (node (ref "Q3") (pin "3") (pinfunction "C2_3") (pintype "passive"))
      (node (ref "R44") (pin "1") (pinfunction "1_1") (pintype "passive"))
    )
    (net (code "94") (name "Net-(Q4-B)") (class "Default")
      (node (ref "Q4") (pin "1") (pinfunction "B_1") (pintype "passive"))
      (node (ref "R40") (pin "2") (pinfunction "2_2") (pintype "passive"))
    )
    (net (code "95") (name "Net-(Q4-C)") (class "Default")
      (node (ref "Q4") (pin "3") (pinfunction "C_3") (pintype "passive"))
      (node (ref "R35") (pin "1") (pinfunction "1_1") (pintype "passive"))
      (node (ref "R37") (pin "2") (pinfunction "2_2") (pintype "passive"))
    )
    (net (code "96") (name "Net-(Q5-C)") (class "Default")
      (node (ref "Q5") (pin "3") (pinfunction "C_3") (pintype "passive"))
      (node (ref "R38") (pin "1") (pinfunction "1_1") (pintype "passive"))
      (node (ref "R40") (pin "1") (pinfunction "1_1") (pintype "passive"))
    )
    (net (code "97") (name "Net-(Q6-C1)") (class "Default")
      (node (ref "Q6") (pin "6") (pinfunction "C1_6") (pintype "passive"))
      (node (ref "R61") (pin "1") (pinfunction "1_1") (pintype "passive"))
    )
    (net (code "98") (name "Net-(Q6-C2)") (class "Default")
      (node (ref "Q6") (pin "3") (pinfunction "C2_3") (pintype "passive"))
      (node (ref "R70") (pin "1") (pinfunction "1_1") (pintype "passive"))
    )
    (net (code "99") (name "Net-(Q7-B)") (class "Default")
      (node (ref "Q7") (pin "1") (pinfunction "B_1") (pintype "passive"))
      (node (ref "R62") (pin "2") (pinfunction "2_2") (pintype "passive"))
    )
    (net (code "100") (name "Net-(Q8-B)") (class "Default")
      (node (ref "Q8") (pin "1") (pinfunction "B_1") (pintype "passive"))
      (node (ref "R66") (pin "2") (pinfunction "2_2") (pintype "passive"))
      (node (ref "R69") (pin "2") (pinfunction "2_2") (pintype "passive"))
    )
    (net (code "101") (name "Net-(Q8-C)") (class "Default")
      (node (ref "Q8") (pin "3") (pinfunction "C_3") (pintype "passive"))
      (node (ref "R60") (pin "1") (pinfunction "1_1") (pintype "passive"))
      (node (ref "R62") (pin "1") (pinfunction "1_1") (pintype "passive"))
    )
    (net (code "102") (name "Net-(Q9-C1)") (class "Default")
      (node (ref "Q9") (pin "6") (pinfunction "C1_6") (pintype "passive"))
      (node (ref "R85") (pin "1") (pinfunction "1_1") (pintype "passive"))
    )
    (net (code "103") (name "Net-(Q9-C2)") (class "Default")
      (node (ref "Q9") (pin "3") (pinfunction "C2_3") (pintype "passive"))
      (node (ref "R89") (pin "1") (pinfunction "1_1") (pintype "passive"))
    )
    (net (code "104") (name "Net-(Q10-C1)") (class "Default")
      (node (ref "Q10") (pin "6") (pinfunction "C1_6") (pintype "passive"))
      (node (ref "R96") (pin "1") (pinfunction "1_1") (pintype "passive"))
    )
    (net (code "105") (name "Net-(Q10-C2)") (class "Default")
      (node (ref "Q10") (pin "3") (pinfunction "C2_3") (pintype "passive"))
      (node (ref "R107") (pin "1") (pinfunction "1_1") (pintype "passive"))
    )
    (net (code "106") (name "Net-(U2-AREF)") (class "Default")
      (node (ref "C4") (pin "1") (pinfunction "1_1") (pintype "passive"))
      (node (ref "U2") (pin "20") (pinfunction "AREF_20") (pintype "passive"))
    )
    (net (code "107") (name "Net-(U2-AVCC)") (class "Default")
      (node (ref "C6") (pin "1") (pinfunction "1_1") (pintype "passive"))
      (node (ref "R8") (pin "2") (pinfunction "2_2") (pintype "passive"))
      (node (ref "U2") (pin "18") (pinfunction "AVCC_18") (pintype "passive"))
    )
    (net (code "108") (name "Net-(U2-PB4)") (class "Default")
      (node (ref "R20") (pin "2") (pinfunction "2_2") (pintype "passive"))
      (node (ref "T5") (pin "1") (pinfunction "1_1") (pintype "passive"))
      (node (ref "U2") (pin "16") (pinfunction "PB4_16") (pintype "passive"))
    )
    (net (code "109") (name "Net-(U2-PB5)") (class "Default")
      (node (ref "R14") (pin "2") (pinfunction "2_2") (pintype "passive"))
      (node (ref "T2") (pin "1") (pinfunction "1_1") (pintype "passive"))
      (node (ref "U2") (pin "17") (pinfunction "PB5_17") (pintype "passive"))
    )
    (net (code "110") (name "Net-(U2-PB6)") (class "Default")
      (node (ref "C5") (pin "1") (pinfunction "1_1") (pintype "passive"))
      (node (ref "U2") (pin "7") (pinfunction "PB6_7") (pintype "passive"))
      (node (ref "X1") (pin "3") (pinfunction "O_3") (pintype "passive"))
    )
    (net (code "111") (name "Net-(U2-PB7)") (class "Default")
      (node (ref "C9") (pin "1") (pinfunction "1_1") (pintype "passive"))
      (node (ref "U2") (pin "8") (pinfunction "PB7_8") (pintype "passive"))
      (node (ref "X1") (pin "1") (pinfunction "I_1") (pintype "passive"))
    )
    (net (code "112") (name "Net-(U6-AREF)") (class "Default")
      (node (ref "C17") (pin "1") (pinfunction "1_1") (pintype "passive"))
      (node (ref "U6") (pin "20") (pinfunction "AREF_20") (pintype "passive"))
    )
    (net (code "113") (name "Net-(U6-AVCC)") (class "Default")
      (node (ref "C19") (pin "1") (pinfunction "1_1") (pintype "passive"))
      (node (ref "R39") (pin "2") (pinfunction "2_2") (pintype "passive"))
      (node (ref "U6") (pin "18") (pinfunction "AVCC_18") (pintype "passive"))
    )
    (net (code "114") (name "Net-(U6-PB4)") (class "Default")
      (node (ref "R53") (pin "2") (pinfunction "2_2") (pintype "passive"))
      (node (ref "T15") (pin "1") (pinfunction "1_1") (pintype "passive"))
      (node (ref "U6") (pin "16") (pinfunction "PB4_16") (pintype "passive"))
    )
    (net (code "115") (name "Net-(U6-PB5)") (class "Default")
      (node (ref "R51") (pin "2") (pinfunction "2_2") (pintype "passive"))
      (node (ref "T13") (pin "1") (pinfunction "1_1") (pintype "passive"))
      (node (ref "U6") (pin "17") (pinfunction "PB5_17") (pintype "passive"))
    )
    (net (code "116") (name "Net-(U6-PB6)") (class "Default")
      (node (ref "C18") (pin "1") (pinfunction "1_1") (pintype "passive"))
      (node (ref "U6") (pin "7") (pinfunction "PB6_7") (pintype "passive"))
      (node (ref "X2") (pin "3") (pinfunction "O_3") (pintype "passive"))
    )
    (net (code "117") (name "Net-(U6-PB7)") (class "Default")
      (node (ref "C24") (pin "1") (pinfunction "1_1") (pintype "passive"))
      (node (ref "U6") (pin "8") (pinfunction "PB7_8") (pintype "passive"))
      (node (ref "X2") (pin "1") (pinfunction "I_1") (pintype "passive"))
    )
    (net (code "118") (name "Net-(U10-AREF)") (class "Default")
      (node (ref "C28") (pin "1") (pinfunction "1_1") (pintype "passive"))
      (node (ref "U10") (pin "20") (pinfunction "AREF_20") (pintype "passive"))
    )
    (net (code "119") (name "Net-(U10-AVCC)") (class "Default")
      (node (ref "C31") (pin "1") (pinfunction "1_1") (pintype "passive"))
      (node (ref "R71") (pin "2") (pinfunction "2_2") (pintype "passive"))
      (node (ref "U10") (pin "18") (pinfunction "AVCC_18") (pintype "passive"))
    )
    (net (code "120") (name "Net-(U10-PB4)") (class "Default")
      (node (ref "R83") (pin "2") (pinfunction "2_2") (pintype "passive"))
      (node (ref "T24") (pin "1") (pinfunction "1_1") (pintype "passive"))
      (node (ref "U10") (pin "16") (pinfunction "PB4_16") (pintype "passive"))
    )
    (net (code "121") (name "Net-(U10-PB5)") (class "Default")
      (node (ref "R80") (pin "2") (pinfunction "2_2") (pintype "passive"))
      (node (ref "T21") (pin "1") (pinfunction "1_1") (pintype "passive"))
      (node (ref "U10") (pin "17") (pinfunction "PB5_17") (pintype "passive"))
    )
    (net (code "122") (name "Net-(U10-PB6)") (class "Default")
      (node (ref "C30") (pin "1") (pinfunction "1_1") (pintype "passive"))
      (node (ref "U10") (pin "7") (pinfunction "PB6_7") (pintype "passive"))
      (node (ref "X3") (pin "3") (pinfunction "O_3") (pintype "passive"))
    )
    (net (code "123") (name "Net-(U10-PB7)") (class "Default")
      (node (ref "C36") (pin "1") (pinfunction "1_1") (pintype "passive"))
      (node (ref "U10") (pin "8") (pinfunction "PB7_8") (pintype "passive"))
      (node (ref "X3") (pin "1") (pinfunction "I_1") (pintype "passive"))
    )
    (net (code "124") (name "Net-(U15-AREF)") (class "Default")
      (node (ref "C41") (pin "1") (pinfunction "1_1") (pintype "passive"))
      (node (ref "U15") (pin "20") (pinfunction "AREF_20") (pintype "passive"))
    )
    (net (code "125") (name "Net-(U15-AVCC)") (class "Default")
      (node (ref "C43") (pin "1") (pinfunction "1_1") (pintype "passive"))
      (node (ref "R95") (pin "2") (pinfunction "2_2") (pintype "passive"))
      (node (ref "U15") (pin "18") (pinfunction "AVCC_18") (pintype "passive"))
    )
    (net (code "126") (name "Net-(U15-PB4)") (class "Default")
      (node (ref "R109") (pin "2") (pinfunction "2_2") (pintype "passive"))
      (node (ref "T33") (pin "1") (pinfunction "1_1") (pintype "passive"))
      (node (ref "U15") (pin "16") (pinfunction "PB4_16") (pintype "passive"))
    )
    (net (code "127") (name "Net-(U15-PB5)") (class "Default")
      (node (ref "R106") (pin "2") (pinfunction "2_2") (pintype "passive"))
      (node (ref "T31") (pin "1") (pinfunction "1_1") (pintype "passive"))
      (node (ref "U15") (pin "17") (pinfunction "PB5_17") (pintype "passive"))
    )
    (net (code "128") (name "Net-(U15-PB6)") (class "Default")
      (node (ref "C42") (pin "1") (pinfunction "1_1") (pintype "passive"))
      (node (ref "U15") (pin "7") (pinfunction "PB6_7") (pintype "passive"))
      (node (ref "X4") (pin "3") (pinfunction "O_3") (pintype "passive"))
    )
    (net (code "129") (name "Net-(U15-PB7)") (class "Default")
      (node (ref "C48") (pin "1") (pinfunction "1_1") (pintype "passive"))
      (node (ref "U15") (pin "8") (pinfunction "PB7_8") (pintype "passive"))
      (node (ref "X4") (pin "1") (pinfunction "I_1") (pintype "passive"))
    )
    (net (code "130") (name "VBAT-1") (class "Default")
      (node (ref "C1") (pin "1") (pinfunction "1_1") (pintype "passive"))
      (node (ref "C10") (pin "1") (pinfunction "1_1") (pintype "passive"))
      (node (ref "C11") (pin "1") (pinfunction "1_1") (pintype "passive"))
      (node (ref "C12") (pin "1") (pinfunction "1_1") (pintype "passive"))
      (node (ref "C13") (pin "1") (pinfunction "1_1") (pintype "passive"))
      (node (ref "C16") (pin "1") (pinfunction "1_1") (pintype "passive"))
      (node (ref "C21") (pin "1") (pinfunction "1_1") (pintype "passive"))
      (node (ref "C22") (pin "1") (pinfunction "1_1") (pintype "passive"))
      (node (ref "C23") (pin "1") (pinfunction "1_1") (pintype "passive"))
      (node (ref "C25") (pin "1") (pinfunction "1_1") (pintype "passive"))
      (node (ref "C29") (pin "1") (pinfunction "1_1") (pintype "passive"))
      (node (ref "C33") (pin "1") (pinfunction "1_1") (pintype "passive"))
      (node (ref "C34") (pin "1") (pinfunction "1_1") (pintype "passive"))
      (node (ref "C35") (pin "1") (pinfunction "1_1") (pintype "passive"))
      (node (ref "C37") (pin "1") (pinfunction "1_1") (pintype "passive"))
      (node (ref "C38") (pin "1") (pinfunction "1_1") (pintype "passive"))
      (node (ref "C45") (pin "1") (pinfunction "1_1") (pintype "passive"))
      (node (ref "C46") (pin "1") (pinfunction "1_1") (pintype "passive"))
      (node (ref "C47") (pin "1") (pinfunction "1_1") (pintype "passive"))
      (node (ref "C8") (pin "1") (pinfunction "1_1") (pintype "passive"))
      (node (ref "R104") (pin "1") (pinfunction "1_1") (pintype "passive"))
      (node (ref "R22") (pin "1") (pinfunction "1_1") (pintype "passive"))
      (node (ref "R27") (pin "1") (pinfunction "1_1") (pintype "passive"))
      (node (ref "R3") (pin "1") (pinfunction "1_1") (pintype "passive"))
      (node (ref "R30") (pin "1") (pinfunction "1_1") (pintype "passive"))
      (node (ref "R41") (pin "1") (pinfunction "1_1") (pintype "passive"))
      (node (ref "R59") (pin "1") (pinfunction "1_1") (pintype "passive"))
      (node (ref "R67") (pin "1") (pinfunction "1_1") (pintype "passive"))
      (node (ref "R82") (pin "1") (pinfunction "1_1") (pintype "passive"))
      (node (ref "R87") (pin "1") (pinfunction "1_1") (pintype "passive"))
      (node (ref "R9") (pin "1") (pinfunction "1_1") (pintype "passive"))
      (node (ref "R94") (pin "1") (pinfunction "1_1") (pintype "passive"))
      (node (ref "U1") (pin "3") (pinfunction "S1_3") (pintype "passive"))
      (node (ref "U11") (pin "3") (pinfunction "S1_3") (pintype "passive"))
      (node (ref "U12") (pin "3") (pinfunction "S1_3") (pintype "passive"))
      (node (ref "U13") (pin "3") (pinfunction "S1_3") (pintype "passive"))
      (node (ref "U14") (pin "3") (pinfunction "S1_3") (pintype "passive"))
      (node (ref "U16") (pin "3") (pinfunction "S1_3") (pintype "passive"))
      (node (ref "U3") (pin "3") (pinfunction "S1_3") (pintype "passive"))
      (node (ref "U4") (pin "3") (pinfunction "S1_3") (pintype "passive"))
      (node (ref "U5") (pin "3") (pinfunction "S1_3") (pintype "passive"))
      (node (ref "U7") (pin "3") (pinfunction "S1_3") (pintype "passive"))
      (node (ref "U8") (pin "3") (pinfunction "S1_3") (pintype "passive"))
      (node (ref "U9") (pin "3") (pinfunction "S1_3") (pintype "passive"))
    )
    (net (code "131") (name "unconnected-(U2-ADC6-Pad19)") (class "Default")
      (node (ref "U2") (pin "19") (pinfunction "ADC6_19") (pintype "passive"))
    )
    (net (code "132") (name "unconnected-(U2-ADC7-Pad22)") (class "Default")
      (node (ref "U2") (pin "22") (pinfunction "ADC7_22") (pintype "passive"))
    )
    (net (code "133") (name "unconnected-(U2-PB0-Pad12)") (class "Default")
      (node (ref "U2") (pin "12") (pinfunction "PB0_12") (pintype "passive"))
    )
    (net (code "134") (name "unconnected-(U2-PC0-Pad23)") (class "Default")
      (node (ref "U2") (pin "23") (pinfunction "PC0_23") (pintype "passive"))
    )
    (net (code "135") (name "unconnected-(U2-PC1-Pad24)") (class "Default")
      (node (ref "U2") (pin "24") (pinfunction "PC1_24") (pintype "passive"))
    )
    (net (code "136") (name "unconnected-(U2-PC2-Pad25)") (class "Default")
      (node (ref "U2") (pin "25") (pinfunction "PC2_25") (pintype "passive"))
    )
    (net (code "137") (name "unconnected-(U2-PC3-Pad26)") (class "Default")
      (node (ref "U2") (pin "26") (pinfunction "PC3_26") (pintype "passive"))
    )
    (net (code "138") (name "unconnected-(U2-PD2-Pad32)") (class "Default")
      (node (ref "U2") (pin "32") (pinfunction "PD2_32") (pintype "passive"))
    )
    (net (code "139") (name "unconnected-(U6-ADC6-Pad19)") (class "Default")
      (node (ref "U6") (pin "19") (pinfunction "ADC6_19") (pintype "passive"))
    )
    (net (code "140") (name "unconnected-(U6-ADC7-Pad22)") (class "Default")
      (node (ref "U6") (pin "22") (pinfunction "ADC7_22") (pintype "passive"))
    )
    (net (code "141") (name "unconnected-(U6-PB0-Pad12)") (class "Default")
      (node (ref "U6") (pin "12") (pinfunction "PB0_12") (pintype "passive"))
    )
    (net (code "142") (name "unconnected-(U6-PC0-Pad23)") (class "Default")
      (node (ref "U6") (pin "23") (pinfunction "PC0_23") (pintype "passive"))
    )
    (net (code "143") (name "unconnected-(U6-PC1-Pad24)") (class "Default")
      (node (ref "U6") (pin "24") (pinfunction "PC1_24") (pintype "passive"))
    )
    (net (code "144") (name "unconnected-(U6-PC2-Pad25)") (class "Default")
      (node (ref "U6") (pin "25") (pinfunction "PC2_25") (pintype "passive"))
    )
    (net (code "145") (name "unconnected-(U6-PC3-Pad26)") (class "Default")
      (node (ref "U6") (pin "26") (pinfunction "PC3_26") (pintype "passive"))
    )
    (net (code "146") (name "unconnected-(U6-PD2-Pad32)") (class "Default")
      (node (ref "U6") (pin "32") (pinfunction "PD2_32") (pintype "passive"))
    )
    (net (code "147") (name "unconnected-(U10-ADC6-Pad19)") (class "Default")
      (node (ref "U10") (pin "19") (pinfunction "ADC6_19") (pintype "passive"))
    )
    (net (code "148") (name "unconnected-(U10-ADC7-Pad22)") (class "Default")
      (node (ref "U10") (pin "22") (pinfunction "ADC7_22") (pintype "passive"))
    )
    (net (code "149") (name "unconnected-(U10-PB0-Pad12)") (class "Default")
      (node (ref "U10") (pin "12") (pinfunction "PB0_12") (pintype "passive"))
    )
    (net (code "150") (name "unconnected-(U10-PC0-Pad23)") (class "Default")
      (node (ref "U10") (pin "23") (pinfunction "PC0_23") (pintype "passive"))
    )
    (net (code "151") (name "unconnected-(U10-PC1-Pad24)") (class "Default")
      (node (ref "U10") (pin "24") (pinfunction "PC1_24") (pintype "passive"))
    )
    (net (code "152") (name "unconnected-(U10-PC2-Pad25)") (class "Default")
      (node (ref "U10") (pin "25") (pinfunction "PC2_25") (pintype "passive"))
    )
    (net (code "153") (name "unconnected-(U10-PC3-Pad26)") (class "Default")
      (node (ref "U10") (pin "26") (pinfunction "PC3_26") (pintype "passive"))
    )
    (net (code "154") (name "unconnected-(U10-PD2-Pad32)") (class "Default")
      (node (ref "U10") (pin "32") (pinfunction "PD2_32") (pintype "passive"))
    )
    (net (code "155") (name "unconnected-(U15-ADC6-Pad19)") (class "Default")
      (node (ref "U15") (pin "19") (pinfunction "ADC6_19") (pintype "passive"))
    )
    (net (code "156") (name "unconnected-(U15-ADC7-Pad22)") (class "Default")
      (node (ref "U15") (pin "22") (pinfunction "ADC7_22") (pintype "passive"))
    )
    (net (code "157") (name "unconnected-(U15-PB0-Pad12)") (class "Default")
      (node (ref "U15") (pin "12") (pinfunction "PB0_12") (pintype "passive"))
    )
    (net (code "158") (name "unconnected-(U15-PC0-Pad23)") (class "Default")
      (node (ref "U15") (pin "23") (pinfunction "PC0_23") (pintype "passive"))
    )
    (net (code "159") (name "unconnected-(U15-PC1-Pad24)") (class "Default")
      (node (ref "U15") (pin "24") (pinfunction "PC1_24") (pintype "passive"))
    )
    (net (code "160") (name "unconnected-(U15-PC2-Pad25)") (class "Default")
      (node (ref "U15") (pin "25") (pinfunction "PC2_25") (pintype "passive"))
    )
    (net (code "161") (name "unconnected-(U15-PC3-Pad26)") (class "Default")
      (node (ref "U15") (pin "26") (pinfunction "PC3_26") (pintype "passive"))
    )
    (net (code "162") (name "unconnected-(U15-PD2-Pad32)") (class "Default")
      (node (ref "U15") (pin "32") (pinfunction "PD2_32") (pintype "passive"))
    )
  )
)
